# eib-256.net
KiCad netlist of a schematic drawn in EAGLE
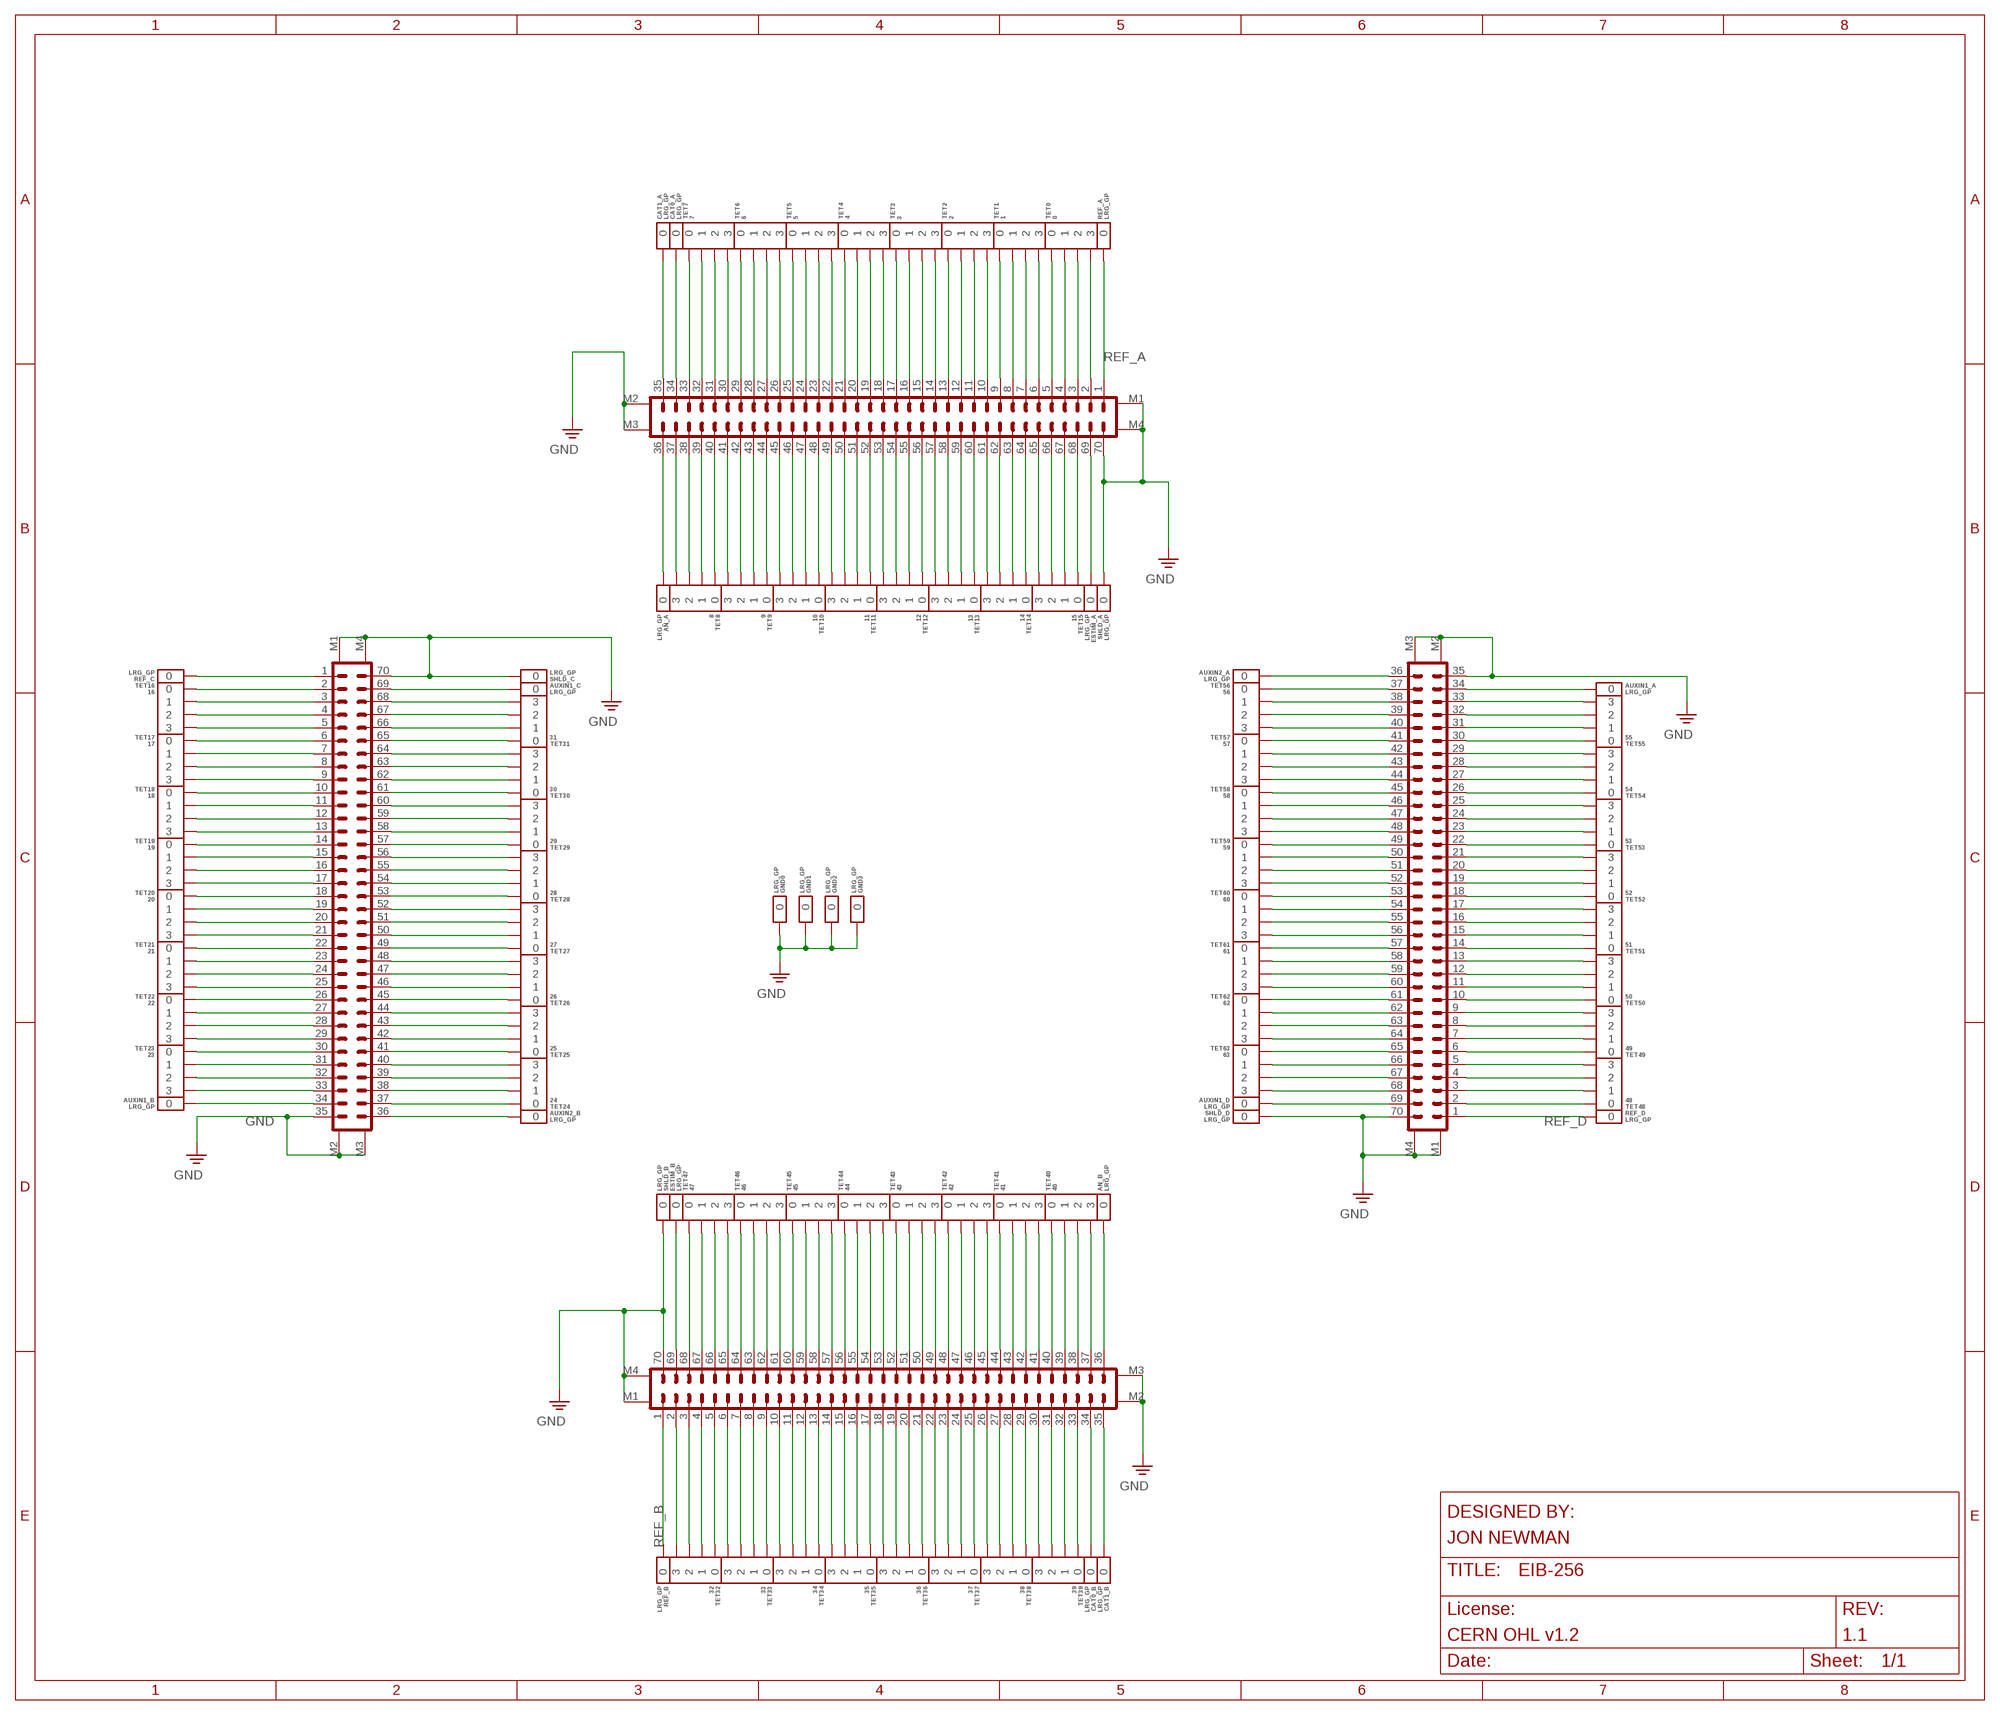
[diagram p0: schematic, sheet 1]

(export (version "E")
  (design (tool "Eeschema 10.0.6"))
  (components
    (comp (ref "A")
      (value "DF40HEAD")
      (footprint "eagle-import:DF40-70HEAD")
      (libsource (lib "eagle-import") (part "PINHD-2X35+4_DF40-70HEAD"))
    )
    (comp (ref "AN_A")
      (value "LRG_GP")
      (footprint "eagle-import:GOLDPIN_0.5ID_0.7OD")
      (libsource (lib "eagle-import") (part "GOLDPIN_0.5ID_0.7OD"))
    )
    (comp (ref "AN_B")
      (value "LRG_GP")
      (footprint "eagle-import:GOLDPIN_0.5ID_0.7OD")
      (libsource (lib "eagle-import") (part "GOLDPIN_0.5ID_0.7OD"))
    )
    (comp (ref "AUXIN1_A")
      (value "LRG_GP")
      (footprint "eagle-import:GOLDPIN_0.5ID_0.7OD")
      (libsource (lib "eagle-import") (part "GOLDPIN_0.5ID_0.7OD"))
    )
    (comp (ref "AUXIN1_B")
      (value "LRG_GP")
      (footprint "eagle-import:GOLDPIN_0.5ID_0.7OD")
      (libsource (lib "eagle-import") (part "GOLDPIN_0.5ID_0.7OD"))
    )
    (comp (ref "AUXIN1_C")
      (value "LRG_GP")
      (footprint "eagle-import:GOLDPIN_0.5ID_0.7OD")
      (libsource (lib "eagle-import") (part "GOLDPIN_0.5ID_0.7OD"))
    )
    (comp (ref "AUXIN1_D")
      (value "LRG_GP")
      (footprint "eagle-import:GOLDPIN_0.5ID_0.7OD")
      (libsource (lib "eagle-import") (part "GOLDPIN_0.5ID_0.7OD"))
    )
    (comp (ref "AUXIN2_A")
      (value "LRG_GP")
      (footprint "eagle-import:GOLDPIN_0.5ID_0.7OD")
      (libsource (lib "eagle-import") (part "GOLDPIN_0.5ID_0.7OD"))
    )
    (comp (ref "AUXIN2_B")
      (value "LRG_GP")
      (footprint "eagle-import:GOLDPIN_0.5ID_0.7OD")
      (libsource (lib "eagle-import") (part "GOLDPIN_0.5ID_0.7OD"))
    )
    (comp (ref "B")
      (value "DF40HEAD")
      (footprint "eagle-import:DF40-70HEAD")
      (libsource (lib "eagle-import") (part "PINHD-2X35+4_DF40-70HEAD"))
    )
    (comp (ref "C")
      (value "DF40HEAD")
      (footprint "eagle-import:DF40-70HEAD")
      (libsource (lib "eagle-import") (part "PINHD-2X35+4_DF40-70HEAD"))
    )
    (comp (ref "CAT0_A")
      (value "LRG_GP")
      (footprint "eagle-import:GOLDPIN_0.5ID_0.7OD")
      (libsource (lib "eagle-import") (part "GOLDPIN_0.5ID_0.7OD"))
    )
    (comp (ref "CAT0_B")
      (value "LRG_GP")
      (footprint "eagle-import:GOLDPIN_0.5ID_0.7OD")
      (libsource (lib "eagle-import") (part "GOLDPIN_0.5ID_0.7OD"))
    )
    (comp (ref "CAT1_A")
      (value "LRG_GP")
      (footprint "eagle-import:GOLDPIN_0.5ID_0.7OD")
      (libsource (lib "eagle-import") (part "GOLDPIN_0.5ID_0.7OD"))
    )
    (comp (ref "CAT1_B")
      (value "LRG_GP")
      (footprint "eagle-import:GOLDPIN_0.5ID_0.7OD")
      (libsource (lib "eagle-import") (part "GOLDPIN_0.5ID_0.7OD"))
    )
    (comp (ref "D")
      (value "DF40HEAD")
      (footprint "eagle-import:DF40-70HEAD")
      (libsource (lib "eagle-import") (part "PINHD-2X35+4_DF40-70HEAD"))
    )
    (comp (ref "ESTIM_A")
      (value "LRG_GP")
      (footprint "eagle-import:GOLDPIN_0.5ID_0.7OD")
      (libsource (lib "eagle-import") (part "GOLDPIN_0.5ID_0.7OD"))
    )
    (comp (ref "ESTIM_B")
      (value "LRG_GP")
      (footprint "eagle-import:GOLDPIN_0.5ID_0.7OD")
      (libsource (lib "eagle-import") (part "GOLDPIN_0.5ID_0.7OD"))
    )
    (comp (ref "GND0")
      (value "LRG_GP")
      (footprint "eagle-import:GOLDPIN_0.5ID_0.7OD")
      (libsource (lib "eagle-import") (part "GOLDPIN_0.5ID_0.7OD"))
    )
    (comp (ref "GND1")
      (value "LRG_GP")
      (footprint "eagle-import:GOLDPIN_0.5ID_0.7OD")
      (libsource (lib "eagle-import") (part "GOLDPIN_0.5ID_0.7OD"))
    )
    (comp (ref "GND2")
      (value "LRG_GP")
      (footprint "eagle-import:GOLDPIN_0.5ID_0.7OD")
      (libsource (lib "eagle-import") (part "GOLDPIN_0.5ID_0.7OD"))
    )
    (comp (ref "GND3")
      (value "LRG_GP")
      (footprint "eagle-import:GOLDPIN_0.5ID_0.7OD")
      (libsource (lib "eagle-import") (part "GOLDPIN_0.5ID_0.7OD"))
    )
    (comp (ref "REF_A")
      (value "LRG_GP")
      (footprint "eagle-import:GOLDPIN_0.5ID_0.7OD")
      (libsource (lib "eagle-import") (part "GOLDPIN_0.5ID_0.7OD"))
    )
    (comp (ref "REF_B")
      (value "LRG_GP")
      (footprint "eagle-import:GOLDPIN_0.5ID_0.7OD")
      (libsource (lib "eagle-import") (part "GOLDPIN_0.5ID_0.7OD"))
    )
    (comp (ref "REF_C")
      (value "LRG_GP")
      (footprint "eagle-import:GOLDPIN_0.5ID_0.7OD")
      (libsource (lib "eagle-import") (part "GOLDPIN_0.5ID_0.7OD"))
    )
    (comp (ref "REF_D")
      (value "LRG_GP")
      (footprint "eagle-import:GOLDPIN_0.5ID_0.7OD")
      (libsource (lib "eagle-import") (part "GOLDPIN_0.5ID_0.7OD"))
    )
    (comp (ref "SHLD_A")
      (value "LRG_GP")
      (footprint "eagle-import:GOLDPIN_0.5ID_0.7OD")
      (libsource (lib "eagle-import") (part "GOLDPIN_0.5ID_0.7OD"))
    )
    (comp (ref "SHLD_B")
      (value "LRG_GP")
      (footprint "eagle-import:GOLDPIN_0.5ID_0.7OD")
      (libsource (lib "eagle-import") (part "GOLDPIN_0.5ID_0.7OD"))
    )
    (comp (ref "SHLD_C")
      (value "LRG_GP")
      (footprint "eagle-import:GOLDPIN_0.5ID_0.7OD")
      (libsource (lib "eagle-import") (part "GOLDPIN_0.5ID_0.7OD"))
    )
    (comp (ref "SHLD_D")
      (value "LRG_GP")
      (footprint "eagle-import:GOLDPIN_0.5ID_0.7OD")
      (libsource (lib "eagle-import") (part "GOLDPIN_0.5ID_0.7OD"))
    )
    (comp (ref "TET0")
      (value "0")
      (footprint "eagle-import:TETRODE_0.3ID_LINEAR")
      (libsource (lib "eagle-import") (part "TETRODE_0.3ID_LINEAR"))
    )
    (comp (ref "TET1")
      (value "1")
      (footprint "eagle-import:TETRODE_0.3ID_LINEAR")
      (libsource (lib "eagle-import") (part "TETRODE_0.3ID_LINEAR"))
    )
    (comp (ref "TET2")
      (value "2")
      (footprint "eagle-import:TETRODE_0.3ID_LINEAR")
      (libsource (lib "eagle-import") (part "TETRODE_0.3ID_LINEAR"))
    )
    (comp (ref "TET3")
      (value "3")
      (footprint "eagle-import:TETRODE_0.3ID_LINEAR")
      (libsource (lib "eagle-import") (part "TETRODE_0.3ID_LINEAR"))
    )
    (comp (ref "TET4")
      (value "4")
      (footprint "eagle-import:TETRODE_0.3ID_LINEAR")
      (libsource (lib "eagle-import") (part "TETRODE_0.3ID_LINEAR"))
    )
    (comp (ref "TET5")
      (value "5")
      (footprint "eagle-import:TETRODE_0.3ID_LINEAR")
      (libsource (lib "eagle-import") (part "TETRODE_0.3ID_LINEAR"))
    )
    (comp (ref "TET6")
      (value "6")
      (footprint "eagle-import:TETRODE_0.3ID_LINEAR")
      (libsource (lib "eagle-import") (part "TETRODE_0.3ID_LINEAR"))
    )
    (comp (ref "TET7")
      (value "7")
      (footprint "eagle-import:TETRODE_0.3ID_LINEAR")
      (libsource (lib "eagle-import") (part "TETRODE_0.3ID_LINEAR"))
    )
    (comp (ref "TET8")
      (value "8")
      (footprint "eagle-import:TETRODE_0.3ID_LINEAR")
      (libsource (lib "eagle-import") (part "TETRODE_0.3ID_LINEAR"))
    )
    (comp (ref "TET9")
      (value "9")
      (footprint "eagle-import:TETRODE_0.3ID_LINEAR")
      (libsource (lib "eagle-import") (part "TETRODE_0.3ID_LINEAR"))
    )
    (comp (ref "TET10")
      (value "10")
      (footprint "eagle-import:TETRODE_0.3ID_LINEAR")
      (libsource (lib "eagle-import") (part "TETRODE_0.3ID_LINEAR"))
    )
    (comp (ref "TET11")
      (value "11")
      (footprint "eagle-import:TETRODE_0.3ID_LINEAR")
      (libsource (lib "eagle-import") (part "TETRODE_0.3ID_LINEAR"))
    )
    (comp (ref "TET12")
      (value "12")
      (footprint "eagle-import:TETRODE_0.3ID_LINEAR")
      (libsource (lib "eagle-import") (part "TETRODE_0.3ID_LINEAR"))
    )
    (comp (ref "TET13")
      (value "13")
      (footprint "eagle-import:TETRODE_0.3ID_LINEAR")
      (libsource (lib "eagle-import") (part "TETRODE_0.3ID_LINEAR"))
    )
    (comp (ref "TET14")
      (value "14")
      (footprint "eagle-import:TETRODE_0.3ID_LINEAR")
      (libsource (lib "eagle-import") (part "TETRODE_0.3ID_LINEAR"))
    )
    (comp (ref "TET15")
      (value "15")
      (footprint "eagle-import:TETRODE_0.3ID_LINEAR")
      (libsource (lib "eagle-import") (part "TETRODE_0.3ID_LINEAR"))
    )
    (comp (ref "TET16")
      (value "16")
      (footprint "eagle-import:TETRODE_0.3ID_LINEAR")
      (libsource (lib "eagle-import") (part "TETRODE_0.3ID_LINEAR"))
    )
    (comp (ref "TET17")
      (value "17")
      (footprint "eagle-import:TETRODE_0.3ID_LINEAR")
      (libsource (lib "eagle-import") (part "TETRODE_0.3ID_LINEAR"))
    )
    (comp (ref "TET18")
      (value "18")
      (footprint "eagle-import:TETRODE_0.3ID_LINEAR")
      (libsource (lib "eagle-import") (part "TETRODE_0.3ID_LINEAR"))
    )
    (comp (ref "TET19")
      (value "19")
      (footprint "eagle-import:TETRODE_0.3ID_LINEAR")
      (libsource (lib "eagle-import") (part "TETRODE_0.3ID_LINEAR"))
    )
    (comp (ref "TET20")
      (value "20")
      (footprint "eagle-import:TETRODE_0.3ID_LINEAR")
      (libsource (lib "eagle-import") (part "TETRODE_0.3ID_LINEAR"))
    )
    (comp (ref "TET21")
      (value "21")
      (footprint "eagle-import:TETRODE_0.3ID_LINEAR")
      (libsource (lib "eagle-import") (part "TETRODE_0.3ID_LINEAR"))
    )
    (comp (ref "TET22")
      (value "22")
      (footprint "eagle-import:TETRODE_0.3ID_LINEAR")
      (libsource (lib "eagle-import") (part "TETRODE_0.3ID_LINEAR"))
    )
    (comp (ref "TET23")
      (value "23")
      (footprint "eagle-import:TETRODE_0.3ID_LINEAR")
      (libsource (lib "eagle-import") (part "TETRODE_0.3ID_LINEAR"))
    )
    (comp (ref "TET24")
      (value "24")
      (footprint "eagle-import:TETRODE_0.3ID_LINEAR")
      (libsource (lib "eagle-import") (part "TETRODE_0.3ID_LINEAR"))
    )
    (comp (ref "TET25")
      (value "25")
      (footprint "eagle-import:TETRODE_0.3ID_LINEAR")
      (libsource (lib "eagle-import") (part "TETRODE_0.3ID_LINEAR"))
    )
    (comp (ref "TET26")
      (value "26")
      (footprint "eagle-import:TETRODE_0.3ID_LINEAR")
      (libsource (lib "eagle-import") (part "TETRODE_0.3ID_LINEAR"))
    )
    (comp (ref "TET27")
      (value "27")
      (footprint "eagle-import:TETRODE_0.3ID_LINEAR")
      (libsource (lib "eagle-import") (part "TETRODE_0.3ID_LINEAR"))
    )
    (comp (ref "TET28")
      (value "28")
      (footprint "eagle-import:TETRODE_0.3ID_LINEAR")
      (libsource (lib "eagle-import") (part "TETRODE_0.3ID_LINEAR"))
    )
    (comp (ref "TET29")
      (value "29")
      (footprint "eagle-import:TETRODE_0.3ID_LINEAR")
      (libsource (lib "eagle-import") (part "TETRODE_0.3ID_LINEAR"))
    )
    (comp (ref "TET30")
      (value "30")
      (footprint "eagle-import:TETRODE_0.3ID_LINEAR")
      (libsource (lib "eagle-import") (part "TETRODE_0.3ID_LINEAR"))
    )
    (comp (ref "TET31")
      (value "31")
      (footprint "eagle-import:TETRODE_0.3ID_LINEAR")
      (libsource (lib "eagle-import") (part "TETRODE_0.3ID_LINEAR"))
    )
    (comp (ref "TET32")
      (value "32")
      (footprint "eagle-import:TETRODE_0.3ID_LINEAR")
      (libsource (lib "eagle-import") (part "TETRODE_0.3ID_LINEAR"))
    )
    (comp (ref "TET33")
      (value "33")
      (footprint "eagle-import:TETRODE_0.3ID_LINEAR")
      (libsource (lib "eagle-import") (part "TETRODE_0.3ID_LINEAR"))
    )
    (comp (ref "TET34")
      (value "34")
      (footprint "eagle-import:TETRODE_0.3ID_LINEAR")
      (libsource (lib "eagle-import") (part "TETRODE_0.3ID_LINEAR"))
    )
    (comp (ref "TET35")
      (value "35")
      (footprint "eagle-import:TETRODE_0.3ID_LINEAR")
      (libsource (lib "eagle-import") (part "TETRODE_0.3ID_LINEAR"))
    )
    (comp (ref "TET36")
      (value "36")
      (footprint "eagle-import:TETRODE_0.3ID_LINEAR")
      (libsource (lib "eagle-import") (part "TETRODE_0.3ID_LINEAR"))
    )
    (comp (ref "TET37")
      (value "37")
      (footprint "eagle-import:TETRODE_0.3ID_LINEAR")
      (libsource (lib "eagle-import") (part "TETRODE_0.3ID_LINEAR"))
    )
    (comp (ref "TET38")
      (value "38")
      (footprint "eagle-import:TETRODE_0.3ID_LINEAR")
      (libsource (lib "eagle-import") (part "TETRODE_0.3ID_LINEAR"))
    )
    (comp (ref "TET39")
      (value "39")
      (footprint "eagle-import:TETRODE_0.3ID_LINEAR")
      (libsource (lib "eagle-import") (part "TETRODE_0.3ID_LINEAR"))
    )
    (comp (ref "TET40")
      (value "40")
      (footprint "eagle-import:TETRODE_0.3ID_LINEAR")
      (libsource (lib "eagle-import") (part "TETRODE_0.3ID_LINEAR"))
    )
    (comp (ref "TET41")
      (value "41")
      (footprint "eagle-import:TETRODE_0.3ID_LINEAR")
      (libsource (lib "eagle-import") (part "TETRODE_0.3ID_LINEAR"))
    )
    (comp (ref "TET42")
      (value "42")
      (footprint "eagle-import:TETRODE_0.3ID_LINEAR")
      (libsource (lib "eagle-import") (part "TETRODE_0.3ID_LINEAR"))
    )
    (comp (ref "TET43")
      (value "43")
      (footprint "eagle-import:TETRODE_0.3ID_LINEAR")
      (libsource (lib "eagle-import") (part "TETRODE_0.3ID_LINEAR"))
    )
    (comp (ref "TET44")
      (value "44")
      (footprint "eagle-import:TETRODE_0.3ID_LINEAR")
      (libsource (lib "eagle-import") (part "TETRODE_0.3ID_LINEAR"))
    )
    (comp (ref "TET45")
      (value "45")
      (footprint "eagle-import:TETRODE_0.3ID_LINEAR")
      (libsource (lib "eagle-import") (part "TETRODE_0.3ID_LINEAR"))
    )
    (comp (ref "TET46")
      (value "46")
      (footprint "eagle-import:TETRODE_0.3ID_LINEAR")
      (libsource (lib "eagle-import") (part "TETRODE_0.3ID_LINEAR"))
    )
    (comp (ref "TET47")
      (value "47")
      (footprint "eagle-import:TETRODE_0.3ID_LINEAR")
      (libsource (lib "eagle-import") (part "TETRODE_0.3ID_LINEAR"))
    )
    (comp (ref "TET48")
      (value "48")
      (footprint "eagle-import:TETRODE_0.3ID_LINEAR")
      (libsource (lib "eagle-import") (part "TETRODE_0.3ID_LINEAR"))
    )
    (comp (ref "TET49")
      (value "49")
      (footprint "eagle-import:TETRODE_0.3ID_LINEAR")
      (libsource (lib "eagle-import") (part "TETRODE_0.3ID_LINEAR"))
    )
    (comp (ref "TET50")
      (value "50")
      (footprint "eagle-import:TETRODE_0.3ID_LINEAR")
      (libsource (lib "eagle-import") (part "TETRODE_0.3ID_LINEAR"))
    )
    (comp (ref "TET51")
      (value "51")
      (footprint "eagle-import:TETRODE_0.3ID_LINEAR")
      (libsource (lib "eagle-import") (part "TETRODE_0.3ID_LINEAR"))
    )
    (comp (ref "TET52")
      (value "52")
      (footprint "eagle-import:TETRODE_0.3ID_LINEAR")
      (libsource (lib "eagle-import") (part "TETRODE_0.3ID_LINEAR"))
    )
    (comp (ref "TET53")
      (value "53")
      (footprint "eagle-import:TETRODE_0.3ID_LINEAR")
      (libsource (lib "eagle-import") (part "TETRODE_0.3ID_LINEAR"))
    )
    (comp (ref "TET54")
      (value "54")
      (footprint "eagle-import:TETRODE_0.3ID_LINEAR")
      (libsource (lib "eagle-import") (part "TETRODE_0.3ID_LINEAR"))
    )
    (comp (ref "TET55")
      (value "55")
      (footprint "eagle-import:TETRODE_0.3ID_LINEAR")
      (libsource (lib "eagle-import") (part "TETRODE_0.3ID_LINEAR"))
    )
    (comp (ref "TET56")
      (value "56")
      (footprint "eagle-import:TETRODE_0.3ID_LINEAR")
      (libsource (lib "eagle-import") (part "TETRODE_0.3ID_LINEAR"))
    )
    (comp (ref "TET57")
      (value "57")
      (footprint "eagle-import:TETRODE_0.3ID_LINEAR")
      (libsource (lib "eagle-import") (part "TETRODE_0.3ID_LINEAR"))
    )
    (comp (ref "TET58")
      (value "58")
      (footprint "eagle-import:TETRODE_0.3ID_LINEAR")
      (libsource (lib "eagle-import") (part "TETRODE_0.3ID_LINEAR"))
    )
    (comp (ref "TET59")
      (value "59")
      (footprint "eagle-import:TETRODE_0.3ID_LINEAR")
      (libsource (lib "eagle-import") (part "TETRODE_0.3ID_LINEAR"))
    )
    (comp (ref "TET60")
      (value "60")
      (footprint "eagle-import:TETRODE_0.3ID_LINEAR")
      (libsource (lib "eagle-import") (part "TETRODE_0.3ID_LINEAR"))
    )
    (comp (ref "TET61")
      (value "61")
      (footprint "eagle-import:TETRODE_0.3ID_LINEAR")
      (libsource (lib "eagle-import") (part "TETRODE_0.3ID_LINEAR"))
    )
    (comp (ref "TET62")
      (value "62")
      (footprint "eagle-import:TETRODE_0.3ID_LINEAR")
      (libsource (lib "eagle-import") (part "TETRODE_0.3ID_LINEAR"))
    )
    (comp (ref "TET63")
      (value "63")
      (footprint "eagle-import:TETRODE_0.3ID_LINEAR")
      (libsource (lib "eagle-import") (part "TETRODE_0.3ID_LINEAR"))
    )
  )
  (nets
    (net (code "1") (name "/REF_A") (class "Default")
      (node (ref "A") (pin "1") (pinfunction "1_1") (pintype "bidirectional"))
      (node (ref "REF_A") (pin "P$1") (pinfunction "0_P$1") (pintype "bidirectional"))
    )
    (net (code "2") (name "/REF_B") (class "Default")
      (node (ref "B") (pin "1") (pinfunction "1_1") (pintype "bidirectional"))
      (node (ref "REF_B") (pin "P$1") (pinfunction "0_P$1") (pintype "bidirectional"))
    )
    (net (code "3") (name "/REF_D") (class "Default")
      (node (ref "D") (pin "1") (pinfunction "1_1") (pintype "bidirectional"))
      (node (ref "REF_D") (pin "P$1") (pinfunction "0_P$1") (pintype "bidirectional"))
    )
    (net (code "4") (name "GND") (class "Default")
      (node (ref "A") (pin "70") (pinfunction "70_70") (pintype "bidirectional"))
      (node (ref "A") (pin "M1") (pinfunction "M1_M1") (pintype "bidirectional"))
      (node (ref "A") (pin "M2") (pinfunction "M2_M2") (pintype "bidirectional"))
      (node (ref "A") (pin "M3") (pinfunction "M3_M3") (pintype "bidirectional"))
      (node (ref "A") (pin "M4") (pinfunction "M4_M4") (pintype "bidirectional"))
      (node (ref "B") (pin "70") (pinfunction "70_70") (pintype "bidirectional"))
      (node (ref "B") (pin "M1") (pinfunction "M1_M1") (pintype "bidirectional"))
      (node (ref "B") (pin "M2") (pinfunction "M2_M2") (pintype "bidirectional"))
      (node (ref "B") (pin "M3") (pinfunction "M3_M3") (pintype "bidirectional"))
      (node (ref "B") (pin "M4") (pinfunction "M4_M4") (pintype "bidirectional"))
      (node (ref "C") (pin "35") (pinfunction "35_35") (pintype "bidirectional"))
      (node (ref "C") (pin "70") (pinfunction "70_70") (pintype "bidirectional"))
      (node (ref "C") (pin "M1") (pinfunction "M1_M1") (pintype "bidirectional"))
      (node (ref "C") (pin "M2") (pinfunction "M2_M2") (pintype "bidirectional"))
      (node (ref "C") (pin "M3") (pinfunction "M3_M3") (pintype "bidirectional"))
      (node (ref "C") (pin "M4") (pinfunction "M4_M4") (pintype "bidirectional"))
      (node (ref "D") (pin "35") (pinfunction "35_35") (pintype "bidirectional"))
      (node (ref "D") (pin "70") (pinfunction "70_70") (pintype "bidirectional"))
      (node (ref "D") (pin "M1") (pinfunction "M1_M1") (pintype "bidirectional"))
      (node (ref "D") (pin "M2") (pinfunction "M2_M2") (pintype "bidirectional"))
      (node (ref "D") (pin "M3") (pinfunction "M3_M3") (pintype "bidirectional"))
      (node (ref "D") (pin "M4") (pinfunction "M4_M4") (pintype "bidirectional"))
      (node (ref "GND0") (pin "P$1") (pinfunction "0_P$1") (pintype "bidirectional"))
      (node (ref "GND1") (pin "P$1") (pinfunction "0_P$1") (pintype "bidirectional"))
      (node (ref "GND2") (pin "P$1") (pinfunction "0_P$1") (pintype "bidirectional"))
      (node (ref "GND3") (pin "P$1") (pinfunction "0_P$1") (pintype "bidirectional"))
      (node (ref "SHLD_A") (pin "P$1") (pinfunction "0_P$1") (pintype "bidirectional"))
      (node (ref "SHLD_B") (pin "P$1") (pinfunction "0_P$1") (pintype "bidirectional"))
      (node (ref "SHLD_C") (pin "P$1") (pinfunction "0_P$1") (pintype "bidirectional"))
      (node (ref "SHLD_D") (pin "P$1") (pinfunction "0_P$1") (pintype "bidirectional"))
    )
    (net (code "5") (name "Net-(A-Pad2)") (class "Default")
      (node (ref "A") (pin "2") (pinfunction "2_2") (pintype "bidirectional"))
      (node (ref "TET0") (pin "3") (pinfunction "3_3") (pintype "bidirectional"))
    )
    (net (code "6") (name "Net-(A-Pad3)") (class "Default")
      (node (ref "A") (pin "3") (pinfunction "3_3") (pintype "bidirectional"))
      (node (ref "TET0") (pin "2") (pinfunction "2_2") (pintype "bidirectional"))
    )
    (net (code "7") (name "Net-(A-Pad4)") (class "Default")
      (node (ref "A") (pin "4") (pinfunction "4_4") (pintype "bidirectional"))
      (node (ref "TET0") (pin "1") (pinfunction "1_1") (pintype "bidirectional"))
    )
    (net (code "8") (name "Net-(A-Pad5)") (class "Default")
      (node (ref "A") (pin "5") (pinfunction "5_5") (pintype "bidirectional"))
      (node (ref "TET0") (pin "0") (pinfunction "0_0") (pintype "bidirectional"))
    )
    (net (code "9") (name "Net-(A-Pad6)") (class "Default")
      (node (ref "A") (pin "6") (pinfunction "6_6") (pintype "bidirectional"))
      (node (ref "TET1") (pin "3") (pinfunction "3_3") (pintype "bidirectional"))
    )
    (net (code "10") (name "Net-(A-Pad7)") (class "Default")
      (node (ref "A") (pin "7") (pinfunction "7_7") (pintype "bidirectional"))
      (node (ref "TET1") (pin "2") (pinfunction "2_2") (pintype "bidirectional"))
    )
    (net (code "11") (name "Net-(A-Pad8)") (class "Default")
      (node (ref "A") (pin "8") (pinfunction "8_8") (pintype "bidirectional"))
      (node (ref "TET1") (pin "1") (pinfunction "1_1") (pintype "bidirectional"))
    )
    (net (code "12") (name "Net-(A-Pad9)") (class "Default")
      (node (ref "A") (pin "9") (pinfunction "9_9") (pintype "bidirectional"))
      (node (ref "TET1") (pin "0") (pinfunction "0_0") (pintype "bidirectional"))
    )
    (net (code "13") (name "Net-(A-Pad10)") (class "Default")
      (node (ref "A") (pin "10") (pinfunction "10_10") (pintype "bidirectional"))
      (node (ref "TET2") (pin "3") (pinfunction "3_3") (pintype "bidirectional"))
    )
    (net (code "14") (name "Net-(A-Pad11)") (class "Default")
      (node (ref "A") (pin "11") (pinfunction "11_11") (pintype "bidirectional"))
      (node (ref "TET2") (pin "2") (pinfunction "2_2") (pintype "bidirectional"))
    )
    (net (code "15") (name "Net-(A-Pad12)") (class "Default")
      (node (ref "A") (pin "12") (pinfunction "12_12") (pintype "bidirectional"))
      (node (ref "TET2") (pin "1") (pinfunction "1_1") (pintype "bidirectional"))
    )
    (net (code "16") (name "Net-(A-Pad13)") (class "Default")
      (node (ref "A") (pin "13") (pinfunction "13_13") (pintype "bidirectional"))
      (node (ref "TET2") (pin "0") (pinfunction "0_0") (pintype "bidirectional"))
    )
    (net (code "17") (name "Net-(A-Pad14)") (class "Default")
      (node (ref "A") (pin "14") (pinfunction "14_14") (pintype "bidirectional"))
      (node (ref "TET3") (pin "3") (pinfunction "3_3") (pintype "bidirectional"))
    )
    (net (code "18") (name "Net-(A-Pad15)") (class "Default")
      (node (ref "A") (pin "15") (pinfunction "15_15") (pintype "bidirectional"))
      (node (ref "TET3") (pin "2") (pinfunction "2_2") (pintype "bidirectional"))
    )
    (net (code "19") (name "Net-(A-Pad16)") (class "Default")
      (node (ref "A") (pin "16") (pinfunction "16_16") (pintype "bidirectional"))
      (node (ref "TET3") (pin "1") (pinfunction "1_1") (pintype "bidirectional"))
    )
    (net (code "20") (name "Net-(A-Pad17)") (class "Default")
      (node (ref "A") (pin "17") (pinfunction "17_17") (pintype "bidirectional"))
      (node (ref "TET3") (pin "0") (pinfunction "0_0") (pintype "bidirectional"))
    )
    (net (code "21") (name "Net-(A-Pad18)") (class "Default")
      (node (ref "A") (pin "18") (pinfunction "18_18") (pintype "bidirectional"))
      (node (ref "TET4") (pin "3") (pinfunction "3_3") (pintype "bidirectional"))
    )
    (net (code "22") (name "Net-(A-Pad19)") (class "Default")
      (node (ref "A") (pin "19") (pinfunction "19_19") (pintype "bidirectional"))
      (node (ref "TET4") (pin "2") (pinfunction "2_2") (pintype "bidirectional"))
    )
    (net (code "23") (name "Net-(A-Pad20)") (class "Default")
      (node (ref "A") (pin "20") (pinfunction "20_20") (pintype "bidirectional"))
      (node (ref "TET4") (pin "1") (pinfunction "1_1") (pintype "bidirectional"))
    )
    (net (code "24") (name "Net-(A-Pad21)") (class "Default")
      (node (ref "A") (pin "21") (pinfunction "21_21") (pintype "bidirectional"))
      (node (ref "TET4") (pin "0") (pinfunction "0_0") (pintype "bidirectional"))
    )
    (net (code "25") (name "Net-(A-Pad22)") (class "Default")
      (node (ref "A") (pin "22") (pinfunction "22_22") (pintype "bidirectional"))
      (node (ref "TET5") (pin "3") (pinfunction "3_3") (pintype "bidirectional"))
    )
    (net (code "26") (name "Net-(A-Pad23)") (class "Default")
      (node (ref "A") (pin "23") (pinfunction "23_23") (pintype "bidirectional"))
      (node (ref "TET5") (pin "2") (pinfunction "2_2") (pintype "bidirectional"))
    )
    (net (code "27") (name "Net-(A-Pad24)") (class "Default")
      (node (ref "A") (pin "24") (pinfunction "24_24") (pintype "bidirectional"))
      (node (ref "TET5") (pin "1") (pinfunction "1_1") (pintype "bidirectional"))
    )
    (net (code "28") (name "Net-(A-Pad25)") (class "Default")
      (node (ref "A") (pin "25") (pinfunction "25_25") (pintype "bidirectional"))
      (node (ref "TET5") (pin "0") (pinfunction "0_0") (pintype "bidirectional"))
    )
    (net (code "29") (name "Net-(A-Pad26)") (class "Default")
      (node (ref "A") (pin "26") (pinfunction "26_26") (pintype "bidirectional"))
      (node (ref "TET6") (pin "3") (pinfunction "3_3") (pintype "bidirectional"))
    )
    (net (code "30") (name "Net-(A-Pad27)") (class "Default")
      (node (ref "A") (pin "27") (pinfunction "27_27") (pintype "bidirectional"))
      (node (ref "TET6") (pin "2") (pinfunction "2_2") (pintype "bidirectional"))
    )
    (net (code "31") (name "Net-(A-Pad28)") (class "Default")
      (node (ref "A") (pin "28") (pinfunction "28_28") (pintype "bidirectional"))
      (node (ref "TET6") (pin "1") (pinfunction "1_1") (pintype "bidirectional"))
    )
    (net (code "32") (name "Net-(A-Pad29)") (class "Default")
      (node (ref "A") (pin "29") (pinfunction "29_29") (pintype "bidirectional"))
      (node (ref "TET6") (pin "0") (pinfunction "0_0") (pintype "bidirectional"))
    )
    (net (code "33") (name "Net-(A-Pad30)") (class "Default")
      (node (ref "A") (pin "30") (pinfunction "30_30") (pintype "bidirectional"))
      (node (ref "TET7") (pin "3") (pinfunction "3_3") (pintype "bidirectional"))
    )
    (net (code "34") (name "Net-(A-Pad31)") (class "Default")
      (node (ref "A") (pin "31") (pinfunction "31_31") (pintype "bidirectional"))
      (node (ref "TET7") (pin "2") (pinfunction "2_2") (pintype "bidirectional"))
    )
    (net (code "35") (name "Net-(A-Pad32)") (class "Default")
      (node (ref "A") (pin "32") (pinfunction "32_32") (pintype "bidirectional"))
      (node (ref "TET7") (pin "1") (pinfunction "1_1") (pintype "bidirectional"))
    )
    (net (code "36") (name "Net-(A-Pad33)") (class "Default")
      (node (ref "A") (pin "33") (pinfunction "33_33") (pintype "bidirectional"))
      (node (ref "TET7") (pin "0") (pinfunction "0_0") (pintype "bidirectional"))
    )
    (net (code "37") (name "Net-(A-Pad37)") (class "Default")
      (node (ref "A") (pin "37") (pinfunction "37_37") (pintype "bidirectional"))
      (node (ref "TET8") (pin "3") (pinfunction "3_3") (pintype "bidirectional"))
    )
    (net (code "38") (name "Net-(A-Pad38)") (class "Default")
      (node (ref "A") (pin "38") (pinfunction "38_38") (pintype "bidirectional"))
      (node (ref "TET8") (pin "2") (pinfunction "2_2") (pintype "bidirectional"))
    )
    (net (code "39") (name "Net-(A-Pad39)") (class "Default")
      (node (ref "A") (pin "39") (pinfunction "39_39") (pintype "bidirectional"))
      (node (ref "TET8") (pin "1") (pinfunction "1_1") (pintype "bidirectional"))
    )
    (net (code "40") (name "Net-(A-Pad40)") (class "Default")
      (node (ref "A") (pin "40") (pinfunction "40_40") (pintype "bidirectional"))
      (node (ref "TET8") (pin "0") (pinfunction "0_0") (pintype "bidirectional"))
    )
    (net (code "41") (name "Net-(A-Pad41)") (class "Default")
      (node (ref "A") (pin "41") (pinfunction "41_41") (pintype "bidirectional"))
      (node (ref "TET9") (pin "3") (pinfunction "3_3") (pintype "bidirectional"))
    )
    (net (code "42") (name "Net-(A-Pad42)") (class "Default")
      (node (ref "A") (pin "42") (pinfunction "42_42") (pintype "bidirectional"))
      (node (ref "TET9") (pin "2") (pinfunction "2_2") (pintype "bidirectional"))
    )
    (net (code "43") (name "Net-(A-Pad43)") (class "Default")
      (node (ref "A") (pin "43") (pinfunction "43_43") (pintype "bidirectional"))
      (node (ref "TET9") (pin "1") (pinfunction "1_1") (pintype "bidirectional"))
    )
    (net (code "44") (name "Net-(A-Pad44)") (class "Default")
      (node (ref "A") (pin "44") (pinfunction "44_44") (pintype "bidirectional"))
      (node (ref "TET9") (pin "0") (pinfunction "0_0") (pintype "bidirectional"))
    )
    (net (code "45") (name "Net-(A-Pad45)") (class "Default")
      (node (ref "A") (pin "45") (pinfunction "45_45") (pintype "bidirectional"))
      (node (ref "TET10") (pin "3") (pinfunction "3_3") (pintype "bidirectional"))
    )
    (net (code "46") (name "Net-(A-Pad46)") (class "Default")
      (node (ref "A") (pin "46") (pinfunction "46_46") (pintype "bidirectional"))
      (node (ref "TET10") (pin "2") (pinfunction "2_2") (pintype "bidirectional"))
    )
    (net (code "47") (name "Net-(A-Pad47)") (class "Default")
      (node (ref "A") (pin "47") (pinfunction "47_47") (pintype "bidirectional"))
      (node (ref "TET10") (pin "1") (pinfunction "1_1") (pintype "bidirectional"))
    )
    (net (code "48") (name "Net-(A-Pad48)") (class "Default")
      (node (ref "A") (pin "48") (pinfunction "48_48") (pintype "bidirectional"))
      (node (ref "TET10") (pin "0") (pinfunction "0_0") (pintype "bidirectional"))
    )
    (net (code "49") (name "Net-(A-Pad49)") (class "Default")
      (node (ref "A") (pin "49") (pinfunction "49_49") (pintype "bidirectional"))
      (node (ref "TET11") (pin "3") (pinfunction "3_3") (pintype "bidirectional"))
    )
    (net (code "50") (name "Net-(A-Pad50)") (class "Default")
      (node (ref "A") (pin "50") (pinfunction "50_50") (pintype "bidirectional"))
      (node (ref "TET11") (pin "2") (pinfunction "2_2") (pintype "bidirectional"))
    )
    (net (code "51") (name "Net-(A-Pad51)") (class "Default")
      (node (ref "A") (pin "51") (pinfunction "51_51") (pintype "bidirectional"))
      (node (ref "TET11") (pin "1") (pinfunction "1_1") (pintype "bidirectional"))
    )
    (net (code "52") (name "Net-(A-Pad52)") (class "Default")
      (node (ref "A") (pin "52") (pinfunction "52_52") (pintype "bidirectional"))
      (node (ref "TET11") (pin "0") (pinfunction "0_0") (pintype "bidirectional"))
    )
    (net (code "53") (name "Net-(A-Pad53)") (class "Default")
      (node (ref "A") (pin "53") (pinfunction "53_53") (pintype "bidirectional"))
      (node (ref "TET12") (pin "3") (pinfunction "3_3") (pintype "bidirectional"))
    )
    (net (code "54") (name "Net-(A-Pad54)") (class "Default")
      (node (ref "A") (pin "54") (pinfunction "54_54") (pintype "bidirectional"))
      (node (ref "TET12") (pin "2") (pinfunction "2_2") (pintype "bidirectional"))
    )
    (net (code "55") (name "Net-(A-Pad55)") (class "Default")
      (node (ref "A") (pin "55") (pinfunction "55_55") (pintype "bidirectional"))
      (node (ref "TET12") (pin "1") (pinfunction "1_1") (pintype "bidirectional"))
    )
    (net (code "56") (name "Net-(A-Pad56)") (class "Default")
      (node (ref "A") (pin "56") (pinfunction "56_56") (pintype "bidirectional"))
      (node (ref "TET12") (pin "0") (pinfunction "0_0") (pintype "bidirectional"))
    )
    (net (code "57") (name "Net-(A-Pad57)") (class "Default")
      (node (ref "A") (pin "57") (pinfunction "57_57") (pintype "bidirectional"))
      (node (ref "TET13") (pin "3") (pinfunction "3_3") (pintype "bidirectional"))
    )
    (net (code "58") (name "Net-(A-Pad58)") (class "Default")
      (node (ref "A") (pin "58") (pinfunction "58_58") (pintype "bidirectional"))
      (node (ref "TET13") (pin "2") (pinfunction "2_2") (pintype "bidirectional"))
    )
    (net (code "59") (name "Net-(A-Pad59)") (class "Default")
      (node (ref "A") (pin "59") (pinfunction "59_59") (pintype "bidirectional"))
      (node (ref "TET13") (pin "1") (pinfunction "1_1") (pintype "bidirectional"))
    )
    (net (code "60") (name "Net-(A-Pad60)") (class "Default")
      (node (ref "A") (pin "60") (pinfunction "60_60") (pintype "bidirectional"))
      (node (ref "TET13") (pin "0") (pinfunction "0_0") (pintype "bidirectional"))
    )
    (net (code "61") (name "Net-(A-Pad61)") (class "Default")
      (node (ref "A") (pin "61") (pinfunction "61_61") (pintype "bidirectional"))
      (node (ref "TET14") (pin "3") (pinfunction "3_3") (pintype "bidirectional"))
    )
    (net (code "62") (name "Net-(A-Pad62)") (class "Default")
      (node (ref "A") (pin "62") (pinfunction "62_62") (pintype "bidirectional"))
      (node (ref "TET14") (pin "2") (pinfunction "2_2") (pintype "bidirectional"))
    )
    (net (code "63") (name "Net-(A-Pad63)") (class "Default")
      (node (ref "A") (pin "63") (pinfunction "63_63") (pintype "bidirectional"))
      (node (ref "TET14") (pin "1") (pinfunction "1_1") (pintype "bidirectional"))
    )
    (net (code "64") (name "Net-(A-Pad64)") (class "Default")
      (node (ref "A") (pin "64") (pinfunction "64_64") (pintype "bidirectional"))
      (node (ref "TET14") (pin "0") (pinfunction "0_0") (pintype "bidirectional"))
    )
    (net (code "65") (name "Net-(A-Pad65)") (class "Default")
      (node (ref "A") (pin "65") (pinfunction "65_65") (pintype "bidirectional"))
      (node (ref "TET15") (pin "3") (pinfunction "3_3") (pintype "bidirectional"))
    )
    (net (code "66") (name "Net-(A-Pad66)") (class "Default")
      (node (ref "A") (pin "66") (pinfunction "66_66") (pintype "bidirectional"))
      (node (ref "TET15") (pin "2") (pinfunction "2_2") (pintype "bidirectional"))
    )
    (net (code "67") (name "Net-(A-Pad67)") (class "Default")
      (node (ref "A") (pin "67") (pinfunction "67_67") (pintype "bidirectional"))
      (node (ref "TET15") (pin "1") (pinfunction "1_1") (pintype "bidirectional"))
    )
    (net (code "68") (name "Net-(A-Pad68)") (class "Default")
      (node (ref "A") (pin "68") (pinfunction "68_68") (pintype "bidirectional"))
      (node (ref "TET15") (pin "0") (pinfunction "0_0") (pintype "bidirectional"))
    )
    (net (code "69") (name "Net-(AN_A-0)") (class "Default")
      (node (ref "A") (pin "36") (pinfunction "36_36") (pintype "bidirectional"))
      (node (ref "AN_A") (pin "P$1") (pinfunction "0_P$1") (pintype "bidirectional"))
    )
    (net (code "70") (name "Net-(AN_B-0)") (class "Default")
      (node (ref "AN_B") (pin "P$1") (pinfunction "0_P$1") (pintype "bidirectional"))
      (node (ref "B") (pin "36") (pinfunction "36_36") (pintype "bidirectional"))
    )
    (net (code "71") (name "Net-(AUXIN1_A-0)") (class "Default")
      (node (ref "AUXIN1_A") (pin "P$1") (pinfunction "0_P$1") (pintype "bidirectional"))
      (node (ref "D") (pin "34") (pinfunction "34_34") (pintype "bidirectional"))
    )
    (net (code "72") (name "Net-(AUXIN1_B-0)") (class "Default")
      (node (ref "AUXIN1_B") (pin "P$1") (pinfunction "0_P$1") (pintype "bidirectional"))
      (node (ref "C") (pin "34") (pinfunction "34_34") (pintype "bidirectional"))
    )
    (net (code "73") (name "Net-(AUXIN1_C-0)") (class "Default")
      (node (ref "AUXIN1_C") (pin "P$1") (pinfunction "0_P$1") (pintype "bidirectional"))
      (node (ref "C") (pin "69") (pinfunction "69_69") (pintype "bidirectional"))
    )
    (net (code "74") (name "Net-(AUXIN1_D-0)") (class "Default")
      (node (ref "AUXIN1_D") (pin "P$1") (pinfunction "0_P$1") (pintype "bidirectional"))
      (node (ref "D") (pin "69") (pinfunction "69_69") (pintype "bidirectional"))
    )
    (net (code "75") (name "Net-(AUXIN2_A-0)") (class "Default")
      (node (ref "AUXIN2_A") (pin "P$1") (pinfunction "0_P$1") (pintype "bidirectional"))
      (node (ref "D") (pin "36") (pinfunction "36_36") (pintype "bidirectional"))
    )
    (net (code "76") (name "Net-(AUXIN2_B-0)") (class "Default")
      (node (ref "AUXIN2_B") (pin "P$1") (pinfunction "0_P$1") (pintype "bidirectional"))
      (node (ref "C") (pin "36") (pinfunction "36_36") (pintype "bidirectional"))
    )
    (net (code "77") (name "Net-(B-Pad2)") (class "Default")
      (node (ref "B") (pin "2") (pinfunction "2_2") (pintype "bidirectional"))
      (node (ref "TET32") (pin "3") (pinfunction "3_3") (pintype "bidirectional"))
    )
    (net (code "78") (name "Net-(B-Pad3)") (class "Default")
      (node (ref "B") (pin "3") (pinfunction "3_3") (pintype "bidirectional"))
      (node (ref "TET32") (pin "2") (pinfunction "2_2") (pintype "bidirectional"))
    )
    (net (code "79") (name "Net-(B-Pad4)") (class "Default")
      (node (ref "B") (pin "4") (pinfunction "4_4") (pintype "bidirectional"))
      (node (ref "TET32") (pin "1") (pinfunction "1_1") (pintype "bidirectional"))
    )
    (net (code "80") (name "Net-(B-Pad5)") (class "Default")
      (node (ref "B") (pin "5") (pinfunction "5_5") (pintype "bidirectional"))
      (node (ref "TET32") (pin "0") (pinfunction "0_0") (pintype "bidirectional"))
    )
    (net (code "81") (name "Net-(B-Pad6)") (class "Default")
      (node (ref "B") (pin "6") (pinfunction "6_6") (pintype "bidirectional"))
      (node (ref "TET33") (pin "3") (pinfunction "3_3") (pintype "bidirectional"))
    )
    (net (code "82") (name "Net-(B-Pad7)") (class "Default")
      (node (ref "B") (pin "7") (pinfunction "7_7") (pintype "bidirectional"))
      (node (ref "TET33") (pin "2") (pinfunction "2_2") (pintype "bidirectional"))
    )
    (net (code "83") (name "Net-(B-Pad8)") (class "Default")
      (node (ref "B") (pin "8") (pinfunction "8_8") (pintype "bidirectional"))
      (node (ref "TET33") (pin "1") (pinfunction "1_1") (pintype "bidirectional"))
    )
    (net (code "84") (name "Net-(B-Pad9)") (class "Default")
      (node (ref "B") (pin "9") (pinfunction "9_9") (pintype "bidirectional"))
      (node (ref "TET33") (pin "0") (pinfunction "0_0") (pintype "bidirectional"))
    )
    (net (code "85") (name "Net-(B-Pad10)") (class "Default")
      (node (ref "B") (pin "10") (pinfunction "10_10") (pintype "bidirectional"))
      (node (ref "TET34") (pin "3") (pinfunction "3_3") (pintype "bidirectional"))
    )
    (net (code "86") (name "Net-(B-Pad11)") (class "Default")
      (node (ref "B") (pin "11") (pinfunction "11_11") (pintype "bidirectional"))
      (node (ref "TET34") (pin "2") (pinfunction "2_2") (pintype "bidirectional"))
    )
    (net (code "87") (name "Net-(B-Pad12)") (class "Default")
      (node (ref "B") (pin "12") (pinfunction "12_12") (pintype "bidirectional"))
      (node (ref "TET34") (pin "1") (pinfunction "1_1") (pintype "bidirectional"))
    )
    (net (code "88") (name "Net-(B-Pad13)") (class "Default")
      (node (ref "B") (pin "13") (pinfunction "13_13") (pintype "bidirectional"))
      (node (ref "TET34") (pin "0") (pinfunction "0_0") (pintype "bidirectional"))
    )
    (net (code "89") (name "Net-(B-Pad14)") (class "Default")
      (node (ref "B") (pin "14") (pinfunction "14_14") (pintype "bidirectional"))
      (node (ref "TET35") (pin "3") (pinfunction "3_3") (pintype "bidirectional"))
    )
    (net (code "90") (name "Net-(B-Pad15)") (class "Default")
      (node (ref "B") (pin "15") (pinfunction "15_15") (pintype "bidirectional"))
      (node (ref "TET35") (pin "2") (pinfunction "2_2") (pintype "bidirectional"))
    )
    (net (code "91") (name "Net-(B-Pad16)") (class "Default")
      (node (ref "B") (pin "16") (pinfunction "16_16") (pintype "bidirectional"))
      (node (ref "TET35") (pin "1") (pinfunction "1_1") (pintype "bidirectional"))
    )
    (net (code "92") (name "Net-(B-Pad17)") (class "Default")
      (node (ref "B") (pin "17") (pinfunction "17_17") (pintype "bidirectional"))
      (node (ref "TET35") (pin "0") (pinfunction "0_0") (pintype "bidirectional"))
    )
    (net (code "93") (name "Net-(B-Pad18)") (class "Default")
      (node (ref "B") (pin "18") (pinfunction "18_18") (pintype "bidirectional"))
      (node (ref "TET36") (pin "3") (pinfunction "3_3") (pintype "bidirectional"))
    )
    (net (code "94") (name "Net-(B-Pad19)") (class "Default")
      (node (ref "B") (pin "19") (pinfunction "19_19") (pintype "bidirectional"))
      (node (ref "TET36") (pin "2") (pinfunction "2_2") (pintype "bidirectional"))
    )
    (net (code "95") (name "Net-(B-Pad20)") (class "Default")
      (node (ref "B") (pin "20") (pinfunction "20_20") (pintype "bidirectional"))
      (node (ref "TET36") (pin "1") (pinfunction "1_1") (pintype "bidirectional"))
    )
    (net (code "96") (name "Net-(B-Pad21)") (class "Default")
      (node (ref "B") (pin "21") (pinfunction "21_21") (pintype "bidirectional"))
      (node (ref "TET36") (pin "0") (pinfunction "0_0") (pintype "bidirectional"))
    )
    (net (code "97") (name "Net-(B-Pad22)") (class "Default")
      (node (ref "B") (pin "22") (pinfunction "22_22") (pintype "bidirectional"))
      (node (ref "TET37") (pin "3") (pinfunction "3_3") (pintype "bidirectional"))
    )
    (net (code "98") (name "Net-(B-Pad23)") (class "Default")
      (node (ref "B") (pin "23") (pinfunction "23_23") (pintype "bidirectional"))
      (node (ref "TET37") (pin "2") (pinfunction "2_2") (pintype "bidirectional"))
    )
    (net (code "99") (name "Net-(B-Pad24)") (class "Default")
      (node (ref "B") (pin "24") (pinfunction "24_24") (pintype "bidirectional"))
      (node (ref "TET37") (pin "1") (pinfunction "1_1") (pintype "bidirectional"))
    )
    (net (code "100") (name "Net-(B-Pad25)") (class "Default")
      (node (ref "B") (pin "25") (pinfunction "25_25") (pintype "bidirectional"))
      (node (ref "TET37") (pin "0") (pinfunction "0_0") (pintype "bidirectional"))
    )
    (net (code "101") (name "Net-(B-Pad26)") (class "Default")
      (node (ref "B") (pin "26") (pinfunction "26_26") (pintype "bidirectional"))
      (node (ref "TET38") (pin "3") (pinfunction "3_3") (pintype "bidirectional"))
    )
    (net (code "102") (name "Net-(B-Pad27)") (class "Default")
      (node (ref "B") (pin "27") (pinfunction "27_27") (pintype "bidirectional"))
      (node (ref "TET38") (pin "2") (pinfunction "2_2") (pintype "bidirectional"))
    )
    (net (code "103") (name "Net-(B-Pad28)") (class "Default")
      (node (ref "B") (pin "28") (pinfunction "28_28") (pintype "bidirectional"))
      (node (ref "TET38") (pin "1") (pinfunction "1_1") (pintype "bidirectional"))
    )
    (net (code "104") (name "Net-(B-Pad29)") (class "Default")
      (node (ref "B") (pin "29") (pinfunction "29_29") (pintype "bidirectional"))
      (node (ref "TET38") (pin "0") (pinfunction "0_0") (pintype "bidirectional"))
    )
    (net (code "105") (name "Net-(B-Pad30)") (class "Default")
      (node (ref "B") (pin "30") (pinfunction "30_30") (pintype "bidirectional"))
      (node (ref "TET39") (pin "3") (pinfunction "3_3") (pintype "bidirectional"))
    )
    (net (code "106") (name "Net-(B-Pad31)") (class "Default")
      (node (ref "B") (pin "31") (pinfunction "31_31") (pintype "bidirectional"))
      (node (ref "TET39") (pin "2") (pinfunction "2_2") (pintype "bidirectional"))
    )
    (net (code "107") (name "Net-(B-Pad32)") (class "Default")
      (node (ref "B") (pin "32") (pinfunction "32_32") (pintype "bidirectional"))
      (node (ref "TET39") (pin "1") (pinfunction "1_1") (pintype "bidirectional"))
    )
    (net (code "108") (name "Net-(B-Pad33)") (class "Default")
      (node (ref "B") (pin "33") (pinfunction "33_33") (pintype "bidirectional"))
      (node (ref "TET39") (pin "0") (pinfunction "0_0") (pintype "bidirectional"))
    )
    (net (code "109") (name "Net-(B-Pad37)") (class "Default")
      (node (ref "B") (pin "37") (pinfunction "37_37") (pintype "bidirectional"))
      (node (ref "TET40") (pin "3") (pinfunction "3_3") (pintype "bidirectional"))
    )
    (net (code "110") (name "Net-(B-Pad38)") (class "Default")
      (node (ref "B") (pin "38") (pinfunction "38_38") (pintype "bidirectional"))
      (node (ref "TET40") (pin "2") (pinfunction "2_2") (pintype "bidirectional"))
    )
    (net (code "111") (name "Net-(B-Pad39)") (class "Default")
      (node (ref "B") (pin "39") (pinfunction "39_39") (pintype "bidirectional"))
      (node (ref "TET40") (pin "1") (pinfunction "1_1") (pintype "bidirectional"))
    )
    (net (code "112") (name "Net-(B-Pad40)") (class "Default")
      (node (ref "B") (pin "40") (pinfunction "40_40") (pintype "bidirectional"))
      (node (ref "TET40") (pin "0") (pinfunction "0_0") (pintype "bidirectional"))
    )
    (net (code "113") (name "Net-(B-Pad41)") (class "Default")
      (node (ref "B") (pin "41") (pinfunction "41_41") (pintype "bidirectional"))
      (node (ref "TET41") (pin "3") (pinfunction "3_3") (pintype "bidirectional"))
    )
    (net (code "114") (name "Net-(B-Pad42)") (class "Default")
      (node (ref "B") (pin "42") (pinfunction "42_42") (pintype "bidirectional"))
      (node (ref "TET41") (pin "2") (pinfunction "2_2") (pintype "bidirectional"))
    )
    (net (code "115") (name "Net-(B-Pad43)") (class "Default")
      (node (ref "B") (pin "43") (pinfunction "43_43") (pintype "bidirectional"))
      (node (ref "TET41") (pin "1") (pinfunction "1_1") (pintype "bidirectional"))
    )
    (net (code "116") (name "Net-(B-Pad44)") (class "Default")
      (node (ref "B") (pin "44") (pinfunction "44_44") (pintype "bidirectional"))
      (node (ref "TET41") (pin "0") (pinfunction "0_0") (pintype "bidirectional"))
    )
    (net (code "117") (name "Net-(B-Pad45)") (class "Default")
      (node (ref "B") (pin "45") (pinfunction "45_45") (pintype "bidirectional"))
      (node (ref "TET42") (pin "3") (pinfunction "3_3") (pintype "bidirectional"))
    )
    (net (code "118") (name "Net-(B-Pad46)") (class "Default")
      (node (ref "B") (pin "46") (pinfunction "46_46") (pintype "bidirectional"))
      (node (ref "TET42") (pin "2") (pinfunction "2_2") (pintype "bidirectional"))
    )
    (net (code "119") (name "Net-(B-Pad47)") (class "Default")
      (node (ref "B") (pin "47") (pinfunction "47_47") (pintype "bidirectional"))
      (node (ref "TET42") (pin "1") (pinfunction "1_1") (pintype "bidirectional"))
    )
    (net (code "120") (name "Net-(B-Pad48)") (class "Default")
      (node (ref "B") (pin "48") (pinfunction "48_48") (pintype "bidirectional"))
      (node (ref "TET42") (pin "0") (pinfunction "0_0") (pintype "bidirectional"))
    )
    (net (code "121") (name "Net-(B-Pad49)") (class "Default")
      (node (ref "B") (pin "49") (pinfunction "49_49") (pintype "bidirectional"))
      (node (ref "TET43") (pin "3") (pinfunction "3_3") (pintype "bidirectional"))
    )
    (net (code "122") (name "Net-(B-Pad50)") (class "Default")
      (node (ref "B") (pin "50") (pinfunction "50_50") (pintype "bidirectional"))
      (node (ref "TET43") (pin "2") (pinfunction "2_2") (pintype "bidirectional"))
    )
    (net (code "123") (name "Net-(B-Pad51)") (class "Default")
      (node (ref "B") (pin "51") (pinfunction "51_51") (pintype "bidirectional"))
      (node (ref "TET43") (pin "1") (pinfunction "1_1") (pintype "bidirectional"))
    )
    (net (code "124") (name "Net-(B-Pad52)") (class "Default")
      (node (ref "B") (pin "52") (pinfunction "52_52") (pintype "bidirectional"))
      (node (ref "TET43") (pin "0") (pinfunction "0_0") (pintype "bidirectional"))
    )
    (net (code "125") (name "Net-(B-Pad53)") (class "Default")
      (node (ref "B") (pin "53") (pinfunction "53_53") (pintype "bidirectional"))
      (node (ref "TET44") (pin "3") (pinfunction "3_3") (pintype "bidirectional"))
    )
    (net (code "126") (name "Net-(B-Pad54)") (class "Default")
      (node (ref "B") (pin "54") (pinfunction "54_54") (pintype "bidirectional"))
      (node (ref "TET44") (pin "2") (pinfunction "2_2") (pintype "bidirectional"))
    )
    (net (code "127") (name "Net-(B-Pad55)") (class "Default")
      (node (ref "B") (pin "55") (pinfunction "55_55") (pintype "bidirectional"))
      (node (ref "TET44") (pin "1") (pinfunction "1_1") (pintype "bidirectional"))
    )
    (net (code "128") (name "Net-(B-Pad56)") (class "Default")
      (node (ref "B") (pin "56") (pinfunction "56_56") (pintype "bidirectional"))
      (node (ref "TET44") (pin "0") (pinfunction "0_0") (pintype "bidirectional"))
    )
    (net (code "129") (name "Net-(B-Pad57)") (class "Default")
      (node (ref "B") (pin "57") (pinfunction "57_57") (pintype "bidirectional"))
      (node (ref "TET45") (pin "3") (pinfunction "3_3") (pintype "bidirectional"))
    )
    (net (code "130") (name "Net-(B-Pad58)") (class "Default")
      (node (ref "B") (pin "58") (pinfunction "58_58") (pintype "bidirectional"))
      (node (ref "TET45") (pin "2") (pinfunction "2_2") (pintype "bidirectional"))
    )
    (net (code "131") (name "Net-(B-Pad59)") (class "Default")
      (node (ref "B") (pin "59") (pinfunction "59_59") (pintype "bidirectional"))
      (node (ref "TET45") (pin "1") (pinfunction "1_1") (pintype "bidirectional"))
    )
    (net (code "132") (name "Net-(B-Pad60)") (class "Default")
      (node (ref "B") (pin "60") (pinfunction "60_60") (pintype "bidirectional"))
      (node (ref "TET45") (pin "0") (pinfunction "0_0") (pintype "bidirectional"))
    )
    (net (code "133") (name "Net-(B-Pad61)") (class "Default")
      (node (ref "B") (pin "61") (pinfunction "61_61") (pintype "bidirectional"))
      (node (ref "TET46") (pin "3") (pinfunction "3_3") (pintype "bidirectional"))
    )
    (net (code "134") (name "Net-(B-Pad62)") (class "Default")
      (node (ref "B") (pin "62") (pinfunction "62_62") (pintype "bidirectional"))
      (node (ref "TET46") (pin "2") (pinfunction "2_2") (pintype "bidirectional"))
    )
    (net (code "135") (name "Net-(B-Pad63)") (class "Default")
      (node (ref "B") (pin "63") (pinfunction "63_63") (pintype "bidirectional"))
      (node (ref "TET46") (pin "1") (pinfunction "1_1") (pintype "bidirectional"))
    )
    (net (code "136") (name "Net-(B-Pad64)") (class "Default")
      (node (ref "B") (pin "64") (pinfunction "64_64") (pintype "bidirectional"))
      (node (ref "TET46") (pin "0") (pinfunction "0_0") (pintype "bidirectional"))
    )
    (net (code "137") (name "Net-(B-Pad65)") (class "Default")
      (node (ref "B") (pin "65") (pinfunction "65_65") (pintype "bidirectional"))
      (node (ref "TET47") (pin "3") (pinfunction "3_3") (pintype "bidirectional"))
    )
    (net (code "138") (name "Net-(B-Pad66)") (class "Default")
      (node (ref "B") (pin "66") (pinfunction "66_66") (pintype "bidirectional"))
      (node (ref "TET47") (pin "2") (pinfunction "2_2") (pintype "bidirectional"))
    )
    (net (code "139") (name "Net-(B-Pad67)") (class "Default")
      (node (ref "B") (pin "67") (pinfunction "67_67") (pintype "bidirectional"))
      (node (ref "TET47") (pin "1") (pinfunction "1_1") (pintype "bidirectional"))
    )
    (net (code "140") (name "Net-(B-Pad68)") (class "Default")
      (node (ref "B") (pin "68") (pinfunction "68_68") (pintype "bidirectional"))
      (node (ref "TET47") (pin "0") (pinfunction "0_0") (pintype "bidirectional"))
    )
    (net (code "141") (name "Net-(C-Pad2)") (class "Default")
      (node (ref "C") (pin "2") (pinfunction "2_2") (pintype "bidirectional"))
      (node (ref "TET16") (pin "0") (pinfunction "0_0") (pintype "bidirectional"))
    )
    (net (code "142") (name "Net-(C-Pad3)") (class "Default")
      (node (ref "C") (pin "3") (pinfunction "3_3") (pintype "bidirectional"))
      (node (ref "TET16") (pin "1") (pinfunction "1_1") (pintype "bidirectional"))
    )
    (net (code "143") (name "Net-(C-Pad4)") (class "Default")
      (node (ref "C") (pin "4") (pinfunction "4_4") (pintype "bidirectional"))
      (node (ref "TET16") (pin "2") (pinfunction "2_2") (pintype "bidirectional"))
    )
    (net (code "144") (name "Net-(C-Pad5)") (class "Default")
      (node (ref "C") (pin "5") (pinfunction "5_5") (pintype "bidirectional"))
      (node (ref "TET16") (pin "3") (pinfunction "3_3") (pintype "bidirectional"))
    )
    (net (code "145") (name "Net-(C-Pad6)") (class "Default")
      (node (ref "C") (pin "6") (pinfunction "6_6") (pintype "bidirectional"))
      (node (ref "TET17") (pin "0") (pinfunction "0_0") (pintype "bidirectional"))
    )
    (net (code "146") (name "Net-(C-Pad7)") (class "Default")
      (node (ref "C") (pin "7") (pinfunction "7_7") (pintype "bidirectional"))
      (node (ref "TET17") (pin "1") (pinfunction "1_1") (pintype "bidirectional"))
    )
    (net (code "147") (name "Net-(C-Pad8)") (class "Default")
      (node (ref "C") (pin "8") (pinfunction "8_8") (pintype "bidirectional"))
      (node (ref "TET17") (pin "2") (pinfunction "2_2") (pintype "bidirectional"))
    )
    (net (code "148") (name "Net-(C-Pad9)") (class "Default")
      (node (ref "C") (pin "9") (pinfunction "9_9") (pintype "bidirectional"))
      (node (ref "TET17") (pin "3") (pinfunction "3_3") (pintype "bidirectional"))
    )
    (net (code "149") (name "Net-(C-Pad10)") (class "Default")
      (node (ref "C") (pin "10") (pinfunction "10_10") (pintype "bidirectional"))
      (node (ref "TET18") (pin "0") (pinfunction "0_0") (pintype "bidirectional"))
    )
    (net (code "150") (name "Net-(C-Pad11)") (class "Default")
      (node (ref "C") (pin "11") (pinfunction "11_11") (pintype "bidirectional"))
      (node (ref "TET18") (pin "1") (pinfunction "1_1") (pintype "bidirectional"))
    )
    (net (code "151") (name "Net-(C-Pad12)") (class "Default")
      (node (ref "C") (pin "12") (pinfunction "12_12") (pintype "bidirectional"))
      (node (ref "TET18") (pin "2") (pinfunction "2_2") (pintype "bidirectional"))
    )
    (net (code "152") (name "Net-(C-Pad13)") (class "Default")
      (node (ref "C") (pin "13") (pinfunction "13_13") (pintype "bidirectional"))
      (node (ref "TET18") (pin "3") (pinfunction "3_3") (pintype "bidirectional"))
    )
    (net (code "153") (name "Net-(C-Pad14)") (class "Default")
      (node (ref "C") (pin "14") (pinfunction "14_14") (pintype "bidirectional"))
      (node (ref "TET19") (pin "0") (pinfunction "0_0") (pintype "bidirectional"))
    )
    (net (code "154") (name "Net-(C-Pad15)") (class "Default")
      (node (ref "C") (pin "15") (pinfunction "15_15") (pintype "bidirectional"))
      (node (ref "TET19") (pin "1") (pinfunction "1_1") (pintype "bidirectional"))
    )
    (net (code "155") (name "Net-(C-Pad16)") (class "Default")
      (node (ref "C") (pin "16") (pinfunction "16_16") (pintype "bidirectional"))
      (node (ref "TET19") (pin "2") (pinfunction "2_2") (pintype "bidirectional"))
    )
    (net (code "156") (name "Net-(C-Pad17)") (class "Default")
      (node (ref "C") (pin "17") (pinfunction "17_17") (pintype "bidirectional"))
      (node (ref "TET19") (pin "3") (pinfunction "3_3") (pintype "bidirectional"))
    )
    (net (code "157") (name "Net-(C-Pad18)") (class "Default")
      (node (ref "C") (pin "18") (pinfunction "18_18") (pintype "bidirectional"))
      (node (ref "TET20") (pin "0") (pinfunction "0_0") (pintype "bidirectional"))
    )
    (net (code "158") (name "Net-(C-Pad19)") (class "Default")
      (node (ref "C") (pin "19") (pinfunction "19_19") (pintype "bidirectional"))
      (node (ref "TET20") (pin "1") (pinfunction "1_1") (pintype "bidirectional"))
    )
    (net (code "159") (name "Net-(C-Pad20)") (class "Default")
      (node (ref "C") (pin "20") (pinfunction "20_20") (pintype "bidirectional"))
      (node (ref "TET20") (pin "2") (pinfunction "2_2") (pintype "bidirectional"))
    )
    (net (code "160") (name "Net-(C-Pad21)") (class "Default")
      (node (ref "C") (pin "21") (pinfunction "21_21") (pintype "bidirectional"))
      (node (ref "TET20") (pin "3") (pinfunction "3_3") (pintype "bidirectional"))
    )
    (net (code "161") (name "Net-(C-Pad22)") (class "Default")
      (node (ref "C") (pin "22") (pinfunction "22_22") (pintype "bidirectional"))
      (node (ref "TET21") (pin "0") (pinfunction "0_0") (pintype "bidirectional"))
    )
    (net (code "162") (name "Net-(C-Pad23)") (class "Default")
      (node (ref "C") (pin "23") (pinfunction "23_23") (pintype "bidirectional"))
      (node (ref "TET21") (pin "1") (pinfunction "1_1") (pintype "bidirectional"))
    )
    (net (code "163") (name "Net-(C-Pad24)") (class "Default")
      (node (ref "C") (pin "24") (pinfunction "24_24") (pintype "bidirectional"))
      (node (ref "TET21") (pin "2") (pinfunction "2_2") (pintype "bidirectional"))
    )
    (net (code "164") (name "Net-(C-Pad25)") (class "Default")
      (node (ref "C") (pin "25") (pinfunction "25_25") (pintype "bidirectional"))
      (node (ref "TET21") (pin "3") (pinfunction "3_3") (pintype "bidirectional"))
    )
    (net (code "165") (name "Net-(C-Pad26)") (class "Default")
      (node (ref "C") (pin "26") (pinfunction "26_26") (pintype "bidirectional"))
      (node (ref "TET22") (pin "0") (pinfunction "0_0") (pintype "bidirectional"))
    )
    (net (code "166") (name "Net-(C-Pad27)") (class "Default")
      (node (ref "C") (pin "27") (pinfunction "27_27") (pintype "bidirectional"))
      (node (ref "TET22") (pin "1") (pinfunction "1_1") (pintype "bidirectional"))
    )
    (net (code "167") (name "Net-(C-Pad28)") (class "Default")
      (node (ref "C") (pin "28") (pinfunction "28_28") (pintype "bidirectional"))
      (node (ref "TET22") (pin "2") (pinfunction "2_2") (pintype "bidirectional"))
    )
    (net (code "168") (name "Net-(C-Pad29)") (class "Default")
      (node (ref "C") (pin "29") (pinfunction "29_29") (pintype "bidirectional"))
      (node (ref "TET22") (pin "3") (pinfunction "3_3") (pintype "bidirectional"))
    )
    (net (code "169") (name "Net-(C-Pad30)") (class "Default")
      (node (ref "C") (pin "30") (pinfunction "30_30") (pintype "bidirectional"))
      (node (ref "TET23") (pin "0") (pinfunction "0_0") (pintype "bidirectional"))
    )
    (net (code "170") (name "Net-(C-Pad31)") (class "Default")
      (node (ref "C") (pin "31") (pinfunction "31_31") (pintype "bidirectional"))
      (node (ref "TET23") (pin "1") (pinfunction "1_1") (pintype "bidirectional"))
    )
    (net (code "171") (name "Net-(C-Pad32)") (class "Default")
      (node (ref "C") (pin "32") (pinfunction "32_32") (pintype "bidirectional"))
      (node (ref "TET23") (pin "2") (pinfunction "2_2") (pintype "bidirectional"))
    )
    (net (code "172") (name "Net-(C-Pad33)") (class "Default")
      (node (ref "C") (pin "33") (pinfunction "33_33") (pintype "bidirectional"))
      (node (ref "TET23") (pin "3") (pinfunction "3_3") (pintype "bidirectional"))
    )
    (net (code "173") (name "Net-(C-Pad37)") (class "Default")
      (node (ref "C") (pin "37") (pinfunction "37_37") (pintype "bidirectional"))
      (node (ref "TET24") (pin "0") (pinfunction "0_0") (pintype "bidirectional"))
    )
    (net (code "174") (name "Net-(C-Pad38)") (class "Default")
      (node (ref "C") (pin "38") (pinfunction "38_38") (pintype "bidirectional"))
      (node (ref "TET24") (pin "1") (pinfunction "1_1") (pintype "bidirectional"))
    )
    (net (code "175") (name "Net-(C-Pad39)") (class "Default")
      (node (ref "C") (pin "39") (pinfunction "39_39") (pintype "bidirectional"))
      (node (ref "TET24") (pin "2") (pinfunction "2_2") (pintype "bidirectional"))
    )
    (net (code "176") (name "Net-(C-Pad40)") (class "Default")
      (node (ref "C") (pin "40") (pinfunction "40_40") (pintype "bidirectional"))
      (node (ref "TET24") (pin "3") (pinfunction "3_3") (pintype "bidirectional"))
    )
    (net (code "177") (name "Net-(C-Pad41)") (class "Default")
      (node (ref "C") (pin "41") (pinfunction "41_41") (pintype "bidirectional"))
      (node (ref "TET25") (pin "0") (pinfunction "0_0") (pintype "bidirectional"))
    )
    (net (code "178") (name "Net-(C-Pad42)") (class "Default")
      (node (ref "C") (pin "42") (pinfunction "42_42") (pintype "bidirectional"))
      (node (ref "TET25") (pin "1") (pinfunction "1_1") (pintype "bidirectional"))
    )
    (net (code "179") (name "Net-(C-Pad43)") (class "Default")
      (node (ref "C") (pin "43") (pinfunction "43_43") (pintype "bidirectional"))
      (node (ref "TET25") (pin "2") (pinfunction "2_2") (pintype "bidirectional"))
    )
    (net (code "180") (name "Net-(C-Pad44)") (class "Default")
      (node (ref "C") (pin "44") (pinfunction "44_44") (pintype "bidirectional"))
      (node (ref "TET25") (pin "3") (pinfunction "3_3") (pintype "bidirectional"))
    )
    (net (code "181") (name "Net-(C-Pad45)") (class "Default")
      (node (ref "C") (pin "45") (pinfunction "45_45") (pintype "bidirectional"))
      (node (ref "TET26") (pin "0") (pinfunction "0_0") (pintype "bidirectional"))
    )
    (net (code "182") (name "Net-(C-Pad46)") (class "Default")
      (node (ref "C") (pin "46") (pinfunction "46_46") (pintype "bidirectional"))
      (node (ref "TET26") (pin "1") (pinfunction "1_1") (pintype "bidirectional"))
    )
    (net (code "183") (name "Net-(C-Pad47)") (class "Default")
      (node (ref "C") (pin "47") (pinfunction "47_47") (pintype "bidirectional"))
      (node (ref "TET26") (pin "2") (pinfunction "2_2") (pintype "bidirectional"))
    )
    (net (code "184") (name "Net-(C-Pad48)") (class "Default")
      (node (ref "C") (pin "48") (pinfunction "48_48") (pintype "bidirectional"))
      (node (ref "TET26") (pin "3") (pinfunction "3_3") (pintype "bidirectional"))
    )
    (net (code "185") (name "Net-(C-Pad49)") (class "Default")
      (node (ref "C") (pin "49") (pinfunction "49_49") (pintype "bidirectional"))
      (node (ref "TET27") (pin "0") (pinfunction "0_0") (pintype "bidirectional"))
    )
    (net (code "186") (name "Net-(C-Pad50)") (class "Default")
      (node (ref "C") (pin "50") (pinfunction "50_50") (pintype "bidirectional"))
      (node (ref "TET27") (pin "1") (pinfunction "1_1") (pintype "bidirectional"))
    )
    (net (code "187") (name "Net-(C-Pad51)") (class "Default")
      (node (ref "C") (pin "51") (pinfunction "51_51") (pintype "bidirectional"))
      (node (ref "TET27") (pin "2") (pinfunction "2_2") (pintype "bidirectional"))
    )
    (net (code "188") (name "Net-(C-Pad52)") (class "Default")
      (node (ref "C") (pin "52") (pinfunction "52_52") (pintype "bidirectional"))
      (node (ref "TET27") (pin "3") (pinfunction "3_3") (pintype "bidirectional"))
    )
    (net (code "189") (name "Net-(C-Pad53)") (class "Default")
      (node (ref "C") (pin "53") (pinfunction "53_53") (pintype "bidirectional"))
      (node (ref "TET28") (pin "0") (pinfunction "0_0") (pintype "bidirectional"))
    )
    (net (code "190") (name "Net-(C-Pad54)") (class "Default")
      (node (ref "C") (pin "54") (pinfunction "54_54") (pintype "bidirectional"))
      (node (ref "TET28") (pin "1") (pinfunction "1_1") (pintype "bidirectional"))
    )
    (net (code "191") (name "Net-(C-Pad55)") (class "Default")
      (node (ref "C") (pin "55") (pinfunction "55_55") (pintype "bidirectional"))
      (node (ref "TET28") (pin "2") (pinfunction "2_2") (pintype "bidirectional"))
    )
    (net (code "192") (name "Net-(C-Pad56)") (class "Default")
      (node (ref "C") (pin "56") (pinfunction "56_56") (pintype "bidirectional"))
      (node (ref "TET28") (pin "3") (pinfunction "3_3") (pintype "bidirectional"))
    )
    (net (code "193") (name "Net-(C-Pad57)") (class "Default")
      (node (ref "C") (pin "57") (pinfunction "57_57") (pintype "bidirectional"))
      (node (ref "TET29") (pin "0") (pinfunction "0_0") (pintype "bidirectional"))
    )
    (net (code "194") (name "Net-(C-Pad58)") (class "Default")
      (node (ref "C") (pin "58") (pinfunction "58_58") (pintype "bidirectional"))
      (node (ref "TET29") (pin "1") (pinfunction "1_1") (pintype "bidirectional"))
    )
    (net (code "195") (name "Net-(C-Pad59)") (class "Default")
      (node (ref "C") (pin "59") (pinfunction "59_59") (pintype "bidirectional"))
      (node (ref "TET29") (pin "2") (pinfunction "2_2") (pintype "bidirectional"))
    )
    (net (code "196") (name "Net-(C-Pad60)") (class "Default")
      (node (ref "C") (pin "60") (pinfunction "60_60") (pintype "bidirectional"))
      (node (ref "TET29") (pin "3") (pinfunction "3_3") (pintype "bidirectional"))
    )
    (net (code "197") (name "Net-(C-Pad61)") (class "Default")
      (node (ref "C") (pin "61") (pinfunction "61_61") (pintype "bidirectional"))
      (node (ref "TET30") (pin "0") (pinfunction "0_0") (pintype "bidirectional"))
    )
    (net (code "198") (name "Net-(C-Pad62)") (class "Default")
      (node (ref "C") (pin "62") (pinfunction "62_62") (pintype "bidirectional"))
      (node (ref "TET30") (pin "1") (pinfunction "1_1") (pintype "bidirectional"))
    )
    (net (code "199") (name "Net-(C-Pad63)") (class "Default")
      (node (ref "C") (pin "63") (pinfunction "63_63") (pintype "bidirectional"))
      (node (ref "TET30") (pin "2") (pinfunction "2_2") (pintype "bidirectional"))
    )
    (net (code "200") (name "Net-(C-Pad64)") (class "Default")
      (node (ref "C") (pin "64") (pinfunction "64_64") (pintype "bidirectional"))
      (node (ref "TET30") (pin "3") (pinfunction "3_3") (pintype "bidirectional"))
    )
    (net (code "201") (name "Net-(C-Pad65)") (class "Default")
      (node (ref "C") (pin "65") (pinfunction "65_65") (pintype "bidirectional"))
      (node (ref "TET31") (pin "0") (pinfunction "0_0") (pintype "bidirectional"))
    )
    (net (code "202") (name "Net-(C-Pad66)") (class "Default")
      (node (ref "C") (pin "66") (pinfunction "66_66") (pintype "bidirectional"))
      (node (ref "TET31") (pin "1") (pinfunction "1_1") (pintype "bidirectional"))
    )
    (net (code "203") (name "Net-(C-Pad67)") (class "Default")
      (node (ref "C") (pin "67") (pinfunction "67_67") (pintype "bidirectional"))
      (node (ref "TET31") (pin "2") (pinfunction "2_2") (pintype "bidirectional"))
    )
    (net (code "204") (name "Net-(C-Pad68)") (class "Default")
      (node (ref "C") (pin "68") (pinfunction "68_68") (pintype "bidirectional"))
      (node (ref "TET31") (pin "3") (pinfunction "3_3") (pintype "bidirectional"))
    )
    (net (code "205") (name "Net-(CAT0_A-0)") (class "Default")
      (node (ref "A") (pin "34") (pinfunction "34_34") (pintype "bidirectional"))
      (node (ref "CAT0_A") (pin "P$1") (pinfunction "0_P$1") (pintype "bidirectional"))
    )
    (net (code "206") (name "Net-(CAT0_B-0)") (class "Default")
      (node (ref "B") (pin "34") (pinfunction "34_34") (pintype "bidirectional"))
      (node (ref "CAT0_B") (pin "P$1") (pinfunction "0_P$1") (pintype "bidirectional"))
    )
    (net (code "207") (name "Net-(CAT1_A-0)") (class "Default")
      (node (ref "A") (pin "35") (pinfunction "35_35") (pintype "bidirectional"))
      (node (ref "CAT1_A") (pin "P$1") (pinfunction "0_P$1") (pintype "bidirectional"))
    )
    (net (code "208") (name "Net-(CAT1_B-0)") (class "Default")
      (node (ref "B") (pin "35") (pinfunction "35_35") (pintype "bidirectional"))
      (node (ref "CAT1_B") (pin "P$1") (pinfunction "0_P$1") (pintype "bidirectional"))
    )
    (net (code "209") (name "Net-(D-Pad2)") (class "Default")
      (node (ref "D") (pin "2") (pinfunction "2_2") (pintype "bidirectional"))
      (node (ref "TET48") (pin "0") (pinfunction "0_0") (pintype "bidirectional"))
    )
    (net (code "210") (name "Net-(D-Pad3)") (class "Default")
      (node (ref "D") (pin "3") (pinfunction "3_3") (pintype "bidirectional"))
      (node (ref "TET48") (pin "1") (pinfunction "1_1") (pintype "bidirectional"))
    )
    (net (code "211") (name "Net-(D-Pad4)") (class "Default")
      (node (ref "D") (pin "4") (pinfunction "4_4") (pintype "bidirectional"))
      (node (ref "TET48") (pin "2") (pinfunction "2_2") (pintype "bidirectional"))
    )
    (net (code "212") (name "Net-(D-Pad5)") (class "Default")
      (node (ref "D") (pin "5") (pinfunction "5_5") (pintype "bidirectional"))
      (node (ref "TET48") (pin "3") (pinfunction "3_3") (pintype "bidirectional"))
    )
    (net (code "213") (name "Net-(D-Pad6)") (class "Default")
      (node (ref "D") (pin "6") (pinfunction "6_6") (pintype "bidirectional"))
      (node (ref "TET49") (pin "0") (pinfunction "0_0") (pintype "bidirectional"))
    )
    (net (code "214") (name "Net-(D-Pad7)") (class "Default")
      (node (ref "D") (pin "7") (pinfunction "7_7") (pintype "bidirectional"))
      (node (ref "TET49") (pin "1") (pinfunction "1_1") (pintype "bidirectional"))
    )
    (net (code "215") (name "Net-(D-Pad8)") (class "Default")
      (node (ref "D") (pin "8") (pinfunction "8_8") (pintype "bidirectional"))
      (node (ref "TET49") (pin "2") (pinfunction "2_2") (pintype "bidirectional"))
    )
    (net (code "216") (name "Net-(D-Pad9)") (class "Default")
      (node (ref "D") (pin "9") (pinfunction "9_9") (pintype "bidirectional"))
      (node (ref "TET49") (pin "3") (pinfunction "3_3") (pintype "bidirectional"))
    )
    (net (code "217") (name "Net-(D-Pad10)") (class "Default")
      (node (ref "D") (pin "10") (pinfunction "10_10") (pintype "bidirectional"))
      (node (ref "TET50") (pin "0") (pinfunction "0_0") (pintype "bidirectional"))
    )
    (net (code "218") (name "Net-(D-Pad11)") (class "Default")
      (node (ref "D") (pin "11") (pinfunction "11_11") (pintype "bidirectional"))
      (node (ref "TET50") (pin "1") (pinfunction "1_1") (pintype "bidirectional"))
    )
    (net (code "219") (name "Net-(D-Pad12)") (class "Default")
      (node (ref "D") (pin "12") (pinfunction "12_12") (pintype "bidirectional"))
      (node (ref "TET50") (pin "2") (pinfunction "2_2") (pintype "bidirectional"))
    )
    (net (code "220") (name "Net-(D-Pad13)") (class "Default")
      (node (ref "D") (pin "13") (pinfunction "13_13") (pintype "bidirectional"))
      (node (ref "TET50") (pin "3") (pinfunction "3_3") (pintype "bidirectional"))
    )
    (net (code "221") (name "Net-(D-Pad14)") (class "Default")
      (node (ref "D") (pin "14") (pinfunction "14_14") (pintype "bidirectional"))
      (node (ref "TET51") (pin "0") (pinfunction "0_0") (pintype "bidirectional"))
    )
    (net (code "222") (name "Net-(D-Pad15)") (class "Default")
      (node (ref "D") (pin "15") (pinfunction "15_15") (pintype "bidirectional"))
      (node (ref "TET51") (pin "1") (pinfunction "1_1") (pintype "bidirectional"))
    )
    (net (code "223") (name "Net-(D-Pad16)") (class "Default")
      (node (ref "D") (pin "16") (pinfunction "16_16") (pintype "bidirectional"))
      (node (ref "TET51") (pin "2") (pinfunction "2_2") (pintype "bidirectional"))
    )
    (net (code "224") (name "Net-(D-Pad17)") (class "Default")
      (node (ref "D") (pin "17") (pinfunction "17_17") (pintype "bidirectional"))
      (node (ref "TET51") (pin "3") (pinfunction "3_3") (pintype "bidirectional"))
    )
    (net (code "225") (name "Net-(D-Pad18)") (class "Default")
      (node (ref "D") (pin "18") (pinfunction "18_18") (pintype "bidirectional"))
      (node (ref "TET52") (pin "0") (pinfunction "0_0") (pintype "bidirectional"))
    )
    (net (code "226") (name "Net-(D-Pad19)") (class "Default")
      (node (ref "D") (pin "19") (pinfunction "19_19") (pintype "bidirectional"))
      (node (ref "TET52") (pin "1") (pinfunction "1_1") (pintype "bidirectional"))
    )
    (net (code "227") (name "Net-(D-Pad20)") (class "Default")
      (node (ref "D") (pin "20") (pinfunction "20_20") (pintype "bidirectional"))
      (node (ref "TET52") (pin "2") (pinfunction "2_2") (pintype "bidirectional"))
    )
    (net (code "228") (name "Net-(D-Pad21)") (class "Default")
      (node (ref "D") (pin "21") (pinfunction "21_21") (pintype "bidirectional"))
      (node (ref "TET52") (pin "3") (pinfunction "3_3") (pintype "bidirectional"))
    )
    (net (code "229") (name "Net-(D-Pad22)") (class "Default")
      (node (ref "D") (pin "22") (pinfunction "22_22") (pintype "bidirectional"))
      (node (ref "TET53") (pin "0") (pinfunction "0_0") (pintype "bidirectional"))
    )
    (net (code "230") (name "Net-(D-Pad23)") (class "Default")
      (node (ref "D") (pin "23") (pinfunction "23_23") (pintype "bidirectional"))
      (node (ref "TET53") (pin "1") (pinfunction "1_1") (pintype "bidirectional"))
    )
    (net (code "231") (name "Net-(D-Pad24)") (class "Default")
      (node (ref "D") (pin "24") (pinfunction "24_24") (pintype "bidirectional"))
      (node (ref "TET53") (pin "2") (pinfunction "2_2") (pintype "bidirectional"))
    )
    (net (code "232") (name "Net-(D-Pad25)") (class "Default")
      (node (ref "D") (pin "25") (pinfunction "25_25") (pintype "bidirectional"))
      (node (ref "TET53") (pin "3") (pinfunction "3_3") (pintype "bidirectional"))
    )
    (net (code "233") (name "Net-(D-Pad26)") (class "Default")
      (node (ref "D") (pin "26") (pinfunction "26_26") (pintype "bidirectional"))
      (node (ref "TET54") (pin "0") (pinfunction "0_0") (pintype "bidirectional"))
    )
    (net (code "234") (name "Net-(D-Pad27)") (class "Default")
      (node (ref "D") (pin "27") (pinfunction "27_27") (pintype "bidirectional"))
      (node (ref "TET54") (pin "1") (pinfunction "1_1") (pintype "bidirectional"))
    )
    (net (code "235") (name "Net-(D-Pad28)") (class "Default")
      (node (ref "D") (pin "28") (pinfunction "28_28") (pintype "bidirectional"))
      (node (ref "TET54") (pin "2") (pinfunction "2_2") (pintype "bidirectional"))
    )
    (net (code "236") (name "Net-(D-Pad29)") (class "Default")
      (node (ref "D") (pin "29") (pinfunction "29_29") (pintype "bidirectional"))
      (node (ref "TET54") (pin "3") (pinfunction "3_3") (pintype "bidirectional"))
    )
    (net (code "237") (name "Net-(D-Pad30)") (class "Default")
      (node (ref "D") (pin "30") (pinfunction "30_30") (pintype "bidirectional"))
      (node (ref "TET55") (pin "0") (pinfunction "0_0") (pintype "bidirectional"))
    )
    (net (code "238") (name "Net-(D-Pad31)") (class "Default")
      (node (ref "D") (pin "31") (pinfunction "31_31") (pintype "bidirectional"))
      (node (ref "TET55") (pin "1") (pinfunction "1_1") (pintype "bidirectional"))
    )
    (net (code "239") (name "Net-(D-Pad32)") (class "Default")
      (node (ref "D") (pin "32") (pinfunction "32_32") (pintype "bidirectional"))
      (node (ref "TET55") (pin "2") (pinfunction "2_2") (pintype "bidirectional"))
    )
    (net (code "240") (name "Net-(D-Pad33)") (class "Default")
      (node (ref "D") (pin "33") (pinfunction "33_33") (pintype "bidirectional"))
      (node (ref "TET55") (pin "3") (pinfunction "3_3") (pintype "bidirectional"))
    )
    (net (code "241") (name "Net-(D-Pad37)") (class "Default")
      (node (ref "D") (pin "37") (pinfunction "37_37") (pintype "bidirectional"))
      (node (ref "TET56") (pin "0") (pinfunction "0_0") (pintype "bidirectional"))
    )
    (net (code "242") (name "Net-(D-Pad38)") (class "Default")
      (node (ref "D") (pin "38") (pinfunction "38_38") (pintype "bidirectional"))
      (node (ref "TET56") (pin "1") (pinfunction "1_1") (pintype "bidirectional"))
    )
    (net (code "243") (name "Net-(D-Pad39)") (class "Default")
      (node (ref "D") (pin "39") (pinfunction "39_39") (pintype "bidirectional"))
      (node (ref "TET56") (pin "2") (pinfunction "2_2") (pintype "bidirectional"))
    )
    (net (code "244") (name "Net-(D-Pad40)") (class "Default")
      (node (ref "D") (pin "40") (pinfunction "40_40") (pintype "bidirectional"))
      (node (ref "TET56") (pin "3") (pinfunction "3_3") (pintype "bidirectional"))
    )
    (net (code "245") (name "Net-(D-Pad41)") (class "Default")
      (node (ref "D") (pin "41") (pinfunction "41_41") (pintype "bidirectional"))
      (node (ref "TET57") (pin "0") (pinfunction "0_0") (pintype "bidirectional"))
    )
    (net (code "246") (name "Net-(D-Pad42)") (class "Default")
      (node (ref "D") (pin "42") (pinfunction "42_42") (pintype "bidirectional"))
      (node (ref "TET57") (pin "1") (pinfunction "1_1") (pintype "bidirectional"))
    )
    (net (code "247") (name "Net-(D-Pad43)") (class "Default")
      (node (ref "D") (pin "43") (pinfunction "43_43") (pintype "bidirectional"))
      (node (ref "TET57") (pin "2") (pinfunction "2_2") (pintype "bidirectional"))
    )
    (net (code "248") (name "Net-(D-Pad44)") (class "Default")
      (node (ref "D") (pin "44") (pinfunction "44_44") (pintype "bidirectional"))
      (node (ref "TET57") (pin "3") (pinfunction "3_3") (pintype "bidirectional"))
    )
    (net (code "249") (name "Net-(D-Pad45)") (class "Default")
      (node (ref "D") (pin "45") (pinfunction "45_45") (pintype "bidirectional"))
      (node (ref "TET58") (pin "0") (pinfunction "0_0") (pintype "bidirectional"))
    )
    (net (code "250") (name "Net-(D-Pad46)") (class "Default")
      (node (ref "D") (pin "46") (pinfunction "46_46") (pintype "bidirectional"))
      (node (ref "TET58") (pin "1") (pinfunction "1_1") (pintype "bidirectional"))
    )
    (net (code "251") (name "Net-(D-Pad47)") (class "Default")
      (node (ref "D") (pin "47") (pinfunction "47_47") (pintype "bidirectional"))
      (node (ref "TET58") (pin "2") (pinfunction "2_2") (pintype "bidirectional"))
    )
    (net (code "252") (name "Net-(D-Pad48)") (class "Default")
      (node (ref "D") (pin "48") (pinfunction "48_48") (pintype "bidirectional"))
      (node (ref "TET58") (pin "3") (pinfunction "3_3") (pintype "bidirectional"))
    )
    (net (code "253") (name "Net-(D-Pad49)") (class "Default")
      (node (ref "D") (pin "49") (pinfunction "49_49") (pintype "bidirectional"))
      (node (ref "TET59") (pin "0") (pinfunction "0_0") (pintype "bidirectional"))
    )
    (net (code "254") (name "Net-(D-Pad50)") (class "Default")
      (node (ref "D") (pin "50") (pinfunction "50_50") (pintype "bidirectional"))
      (node (ref "TET59") (pin "1") (pinfunction "1_1") (pintype "bidirectional"))
    )
    (net (code "255") (name "Net-(D-Pad51)") (class "Default")
      (node (ref "D") (pin "51") (pinfunction "51_51") (pintype "bidirectional"))
      (node (ref "TET59") (pin "2") (pinfunction "2_2") (pintype "bidirectional"))
    )
    (net (code "256") (name "Net-(D-Pad52)") (class "Default")
      (node (ref "D") (pin "52") (pinfunction "52_52") (pintype "bidirectional"))
      (node (ref "TET59") (pin "3") (pinfunction "3_3") (pintype "bidirectional"))
    )
    (net (code "257") (name "Net-(D-Pad53)") (class "Default")
      (node (ref "D") (pin "53") (pinfunction "53_53") (pintype "bidirectional"))
      (node (ref "TET60") (pin "0") (pinfunction "0_0") (pintype "bidirectional"))
    )
    (net (code "258") (name "Net-(D-Pad54)") (class "Default")
      (node (ref "D") (pin "54") (pinfunction "54_54") (pintype "bidirectional"))
      (node (ref "TET60") (pin "1") (pinfunction "1_1") (pintype "bidirectional"))
    )
    (net (code "259") (name "Net-(D-Pad55)") (class "Default")
      (node (ref "D") (pin "55") (pinfunction "55_55") (pintype "bidirectional"))
      (node (ref "TET60") (pin "2") (pinfunction "2_2") (pintype "bidirectional"))
    )
    (net (code "260") (name "Net-(D-Pad56)") (class "Default")
      (node (ref "D") (pin "56") (pinfunction "56_56") (pintype "bidirectional"))
      (node (ref "TET60") (pin "3") (pinfunction "3_3") (pintype "bidirectional"))
    )
    (net (code "261") (name "Net-(D-Pad57)") (class "Default")
      (node (ref "D") (pin "57") (pinfunction "57_57") (pintype "bidirectional"))
      (node (ref "TET61") (pin "0") (pinfunction "0_0") (pintype "bidirectional"))
    )
    (net (code "262") (name "Net-(D-Pad58)") (class "Default")
      (node (ref "D") (pin "58") (pinfunction "58_58") (pintype "bidirectional"))
      (node (ref "TET61") (pin "1") (pinfunction "1_1") (pintype "bidirectional"))
    )
    (net (code "263") (name "Net-(D-Pad59)") (class "Default")
      (node (ref "D") (pin "59") (pinfunction "59_59") (pintype "bidirectional"))
      (node (ref "TET61") (pin "2") (pinfunction "2_2") (pintype "bidirectional"))
    )
    (net (code "264") (name "Net-(D-Pad60)") (class "Default")
      (node (ref "D") (pin "60") (pinfunction "60_60") (pintype "bidirectional"))
      (node (ref "TET61") (pin "3") (pinfunction "3_3") (pintype "bidirectional"))
    )
    (net (code "265") (name "Net-(D-Pad61)") (class "Default")
      (node (ref "D") (pin "61") (pinfunction "61_61") (pintype "bidirectional"))
      (node (ref "TET62") (pin "0") (pinfunction "0_0") (pintype "bidirectional"))
    )
    (net (code "266") (name "Net-(D-Pad62)") (class "Default")
      (node (ref "D") (pin "62") (pinfunction "62_62") (pintype "bidirectional"))
      (node (ref "TET62") (pin "1") (pinfunction "1_1") (pintype "bidirectional"))
    )
    (net (code "267") (name "Net-(D-Pad63)") (class "Default")
      (node (ref "D") (pin "63") (pinfunction "63_63") (pintype "bidirectional"))
      (node (ref "TET62") (pin "2") (pinfunction "2_2") (pintype "bidirectional"))
    )
    (net (code "268") (name "Net-(D-Pad64)") (class "Default")
      (node (ref "D") (pin "64") (pinfunction "64_64") (pintype "bidirectional"))
      (node (ref "TET62") (pin "3") (pinfunction "3_3") (pintype "bidirectional"))
    )
    (net (code "269") (name "Net-(D-Pad65)") (class "Default")
      (node (ref "D") (pin "65") (pinfunction "65_65") (pintype "bidirectional"))
      (node (ref "TET63") (pin "0") (pinfunction "0_0") (pintype "bidirectional"))
    )
    (net (code "270") (name "Net-(D-Pad66)") (class "Default")
      (node (ref "D") (pin "66") (pinfunction "66_66") (pintype "bidirectional"))
      (node (ref "TET63") (pin "1") (pinfunction "1_1") (pintype "bidirectional"))
    )
    (net (code "271") (name "Net-(D-Pad67)") (class "Default")
      (node (ref "D") (pin "67") (pinfunction "67_67") (pintype "bidirectional"))
      (node (ref "TET63") (pin "2") (pinfunction "2_2") (pintype "bidirectional"))
    )
    (net (code "272") (name "Net-(D-Pad68)") (class "Default")
      (node (ref "D") (pin "68") (pinfunction "68_68") (pintype "bidirectional"))
      (node (ref "TET63") (pin "3") (pinfunction "3_3") (pintype "bidirectional"))
    )
    (net (code "273") (name "Net-(ESTIM_A-0)") (class "Default")
      (node (ref "A") (pin "69") (pinfunction "69_69") (pintype "bidirectional"))
      (node (ref "ESTIM_A") (pin "P$1") (pinfunction "0_P$1") (pintype "bidirectional"))
    )
    (net (code "274") (name "Net-(ESTIM_B-0)") (class "Default")
      (node (ref "B") (pin "69") (pinfunction "69_69") (pintype "bidirectional"))
      (node (ref "ESTIM_B") (pin "P$1") (pinfunction "0_P$1") (pintype "bidirectional"))
    )
    (net (code "275") (name "Net-(REF_C-0)") (class "Default")
      (node (ref "C") (pin "1") (pinfunction "1_1") (pintype "bidirectional"))
      (node (ref "REF_C") (pin "P$1") (pinfunction "0_P$1") (pintype "bidirectional"))
    )
  )
)
